# slimarm_apricot_dev.net
KiCad netlist of a schematic drawn in EasyEDA Pro
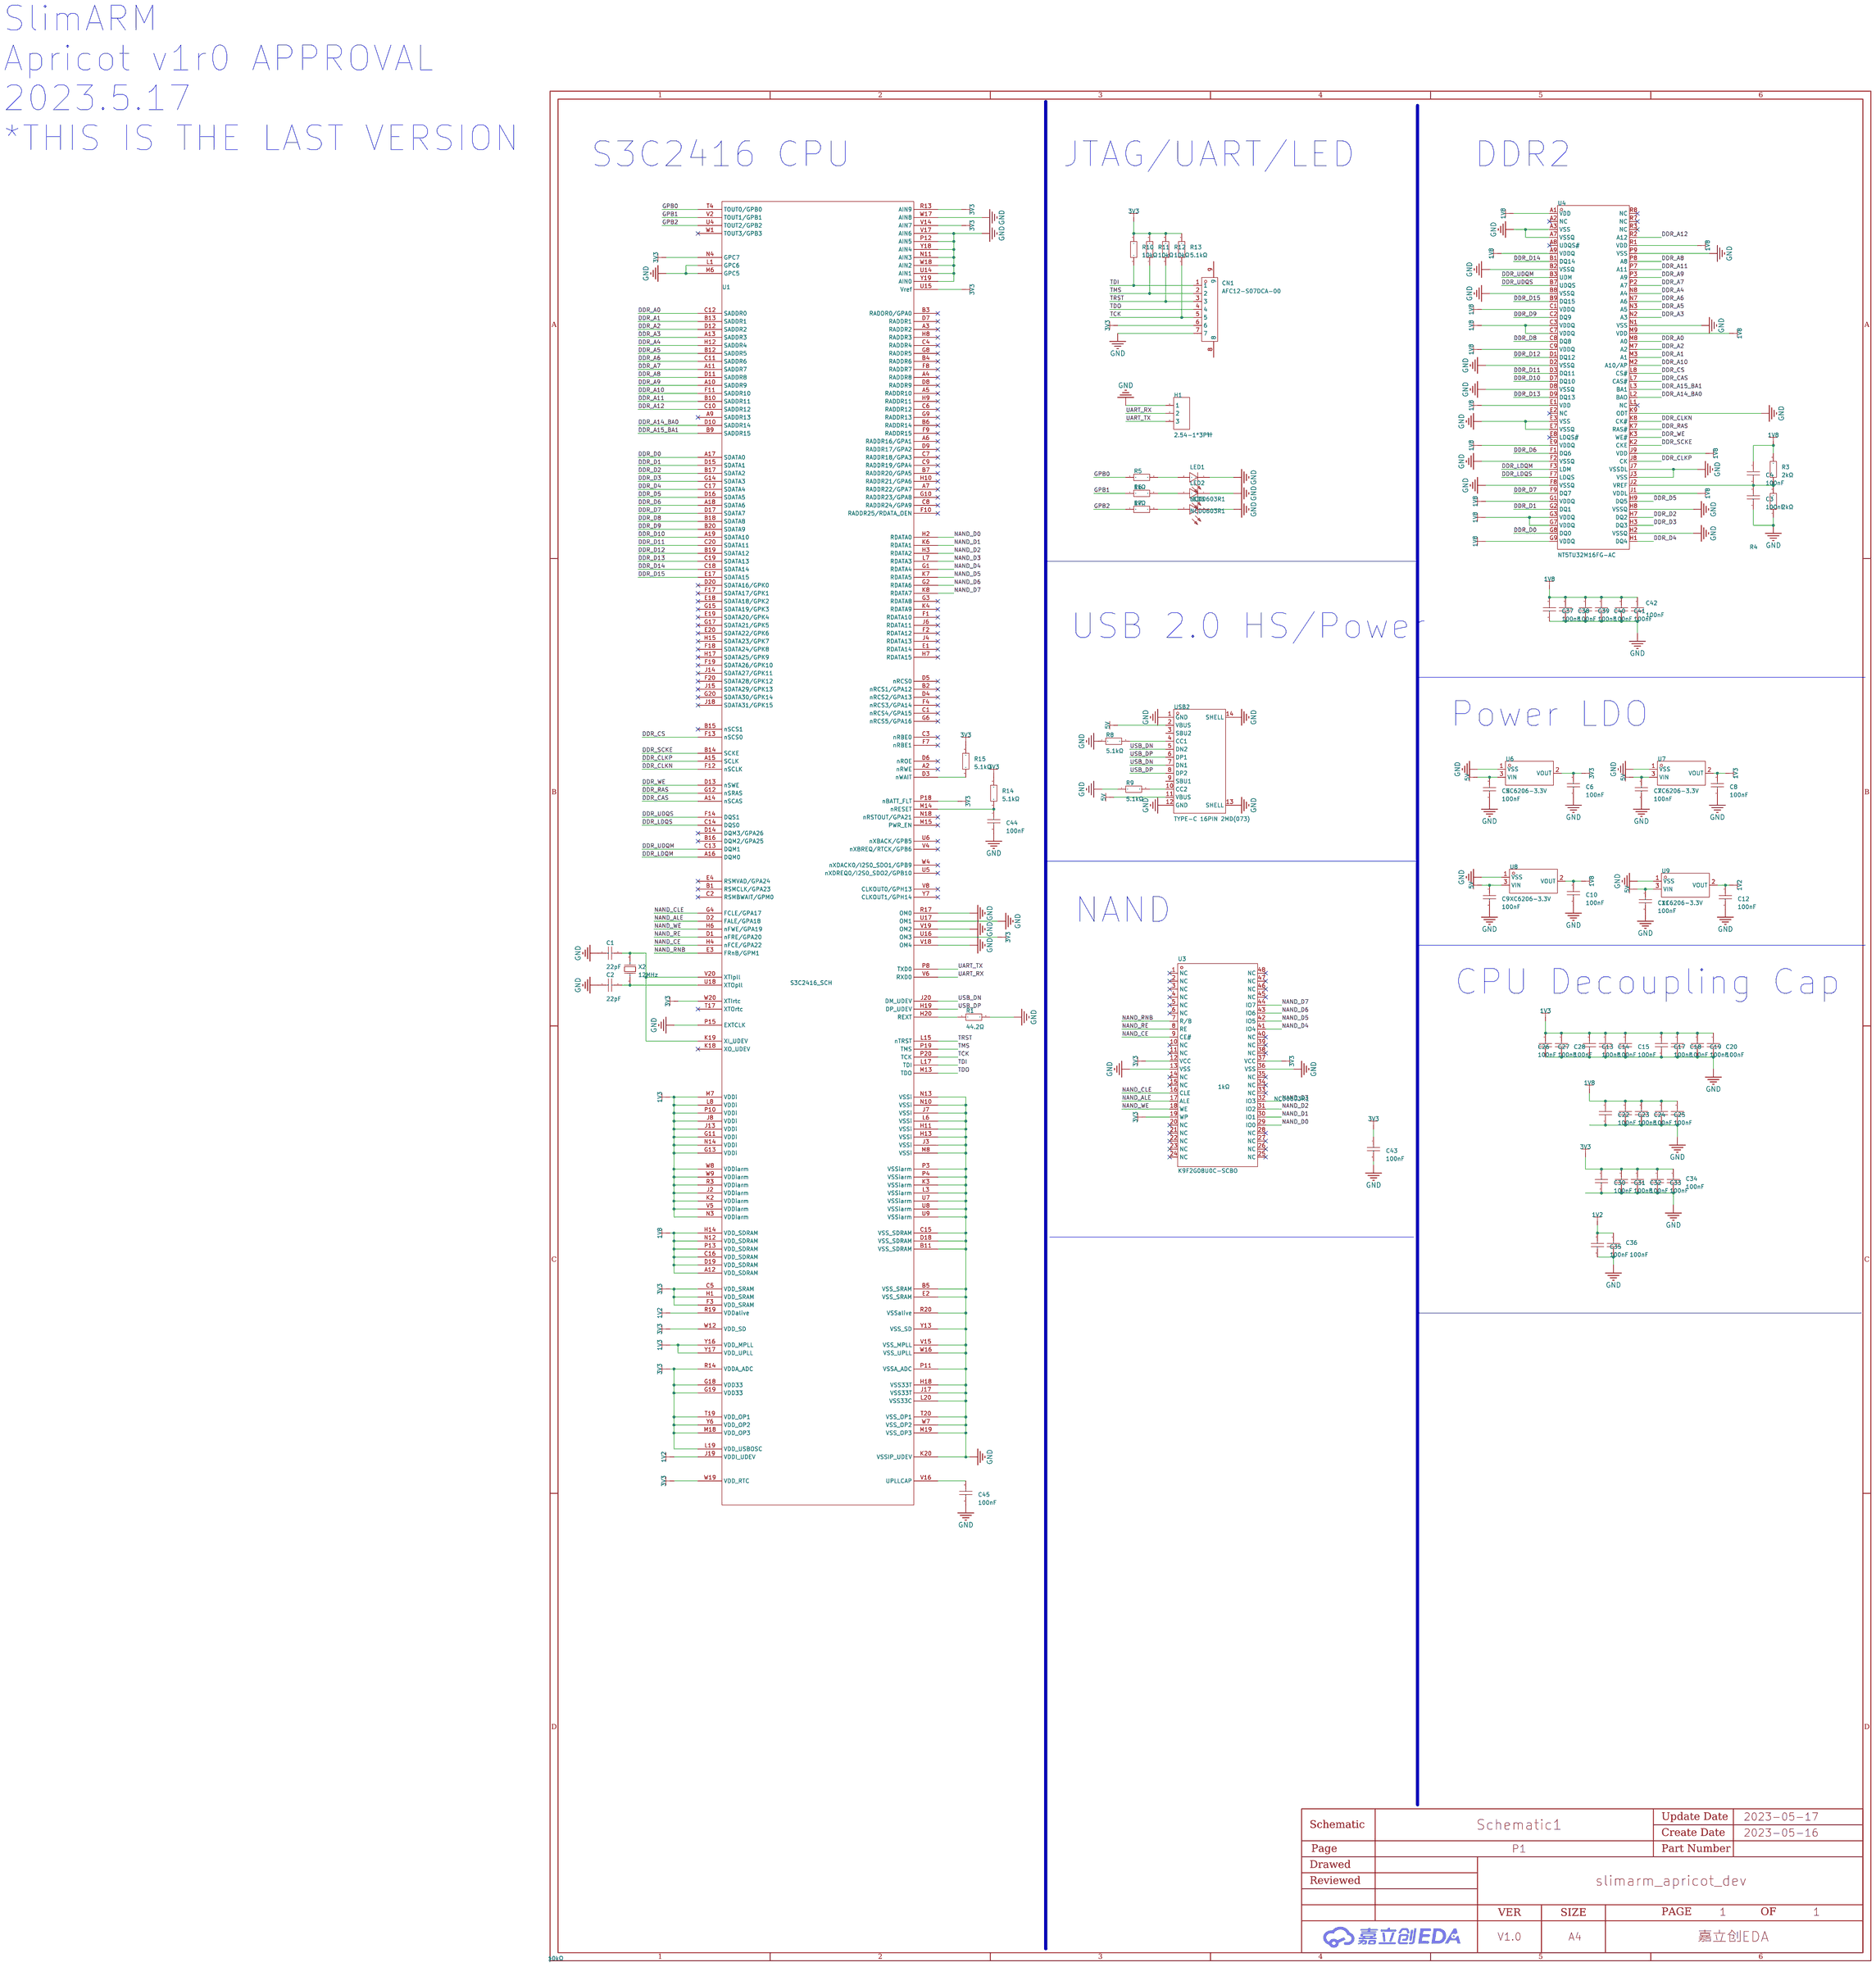
[diagram p0: schematic sheet]

(export (version "E")
  (design (tool "Eeschema 10.0.6"))
  (components
    (comp (ref "C1")
      (value "22pF")
      (footprint "easyedapro:C0402")
      (description "容值:22pF;精度:±5%;额定电压:50V;材质(温度系数):NP0;")
      (fields
        (field (name "Manufacturer Part") "CC0402JRNPO9BN220")
        (field (name "Manufacturer") "YAGEO(国巨)")
      )
      (libsource (lib "easyedapro") (part "CC0402JRNPO9BN220"))
    )
    (comp (ref "C2")
      (value "22pF")
      (footprint "easyedapro:C0402")
      (description "容值:22pF;精度:±5%;额定电压:50V;材质(温度系数):NP0;")
      (fields
        (field (name "Manufacturer Part") "CC0402JRNPO9BN220")
        (field (name "Manufacturer") "YAGEO(国巨)")
      )
      (libsource (lib "easyedapro") (part "CC0402JRNPO9BN220"))
    )
    (comp (ref "C3")
      (value "100nF")
      (footprint "easyedapro:C0402")
      (description "容值:22pF;精度:±5%;额定电压:50V;材质(温度系数):NP0;")
      (fields
        (field (name "Manufacturer Part") "CC0402JRNPO9BN220")
        (field (name "Manufacturer") "YAGEO(国巨)")
      )
      (libsource (lib "easyedapro") (part "CC0402JRNPO9BN220"))
    )
    (comp (ref "C4")
      (value "100nF")
      (footprint "easyedapro:C0402")
      (description "容值:22pF;精度:±5%;额定电压:50V;材质(温度系数):NP0;")
      (fields
        (field (name "Manufacturer Part") "CC0402JRNPO9BN220")
        (field (name "Manufacturer") "YAGEO(国巨)")
      )
      (libsource (lib "easyedapro") (part "CC0402JRNPO9BN220"))
    )
    (comp (ref "C5")
      (value "100nF")
      (footprint "easyedapro:C0402")
      (description "容值:22pF;精度:±5%;额定电压:50V;材质(温度系数):NP0;")
      (fields
        (field (name "Manufacturer Part") "CC0402JRNPO9BN220")
        (field (name "Manufacturer") "YAGEO(国巨)")
      )
      (libsource (lib "easyedapro") (part "CC0402JRNPO9BN220"))
    )
    (comp (ref "C6")
      (value "100nF")
      (footprint "easyedapro:C0402")
      (description "容值:22pF;精度:±5%;额定电压:50V;材质(温度系数):NP0;")
      (fields
        (field (name "Manufacturer Part") "CC0402JRNPO9BN220")
        (field (name "Manufacturer") "YAGEO(国巨)")
      )
      (libsource (lib "easyedapro") (part "CC0402JRNPO9BN220"))
    )
    (comp (ref "C7")
      (value "100nF")
      (footprint "easyedapro:C0402")
      (description "容值:22pF;精度:±5%;额定电压:50V;材质(温度系数):NP0;")
      (fields
        (field (name "Manufacturer Part") "CC0402JRNPO9BN220")
        (field (name "Manufacturer") "YAGEO(国巨)")
      )
      (libsource (lib "easyedapro") (part "CC0402JRNPO9BN220"))
    )
    (comp (ref "C8")
      (value "100nF")
      (footprint "easyedapro:C0402")
      (description "容值:22pF;精度:±5%;额定电压:50V;材质(温度系数):NP0;")
      (fields
        (field (name "Manufacturer Part") "CC0402JRNPO9BN220")
        (field (name "Manufacturer") "YAGEO(国巨)")
      )
      (libsource (lib "easyedapro") (part "CC0402JRNPO9BN220"))
    )
    (comp (ref "C9")
      (value "100nF")
      (footprint "easyedapro:C0402")
      (description "容值:22pF;精度:±5%;额定电压:50V;材质(温度系数):NP0;")
      (fields
        (field (name "Manufacturer Part") "CC0402JRNPO9BN220")
        (field (name "Manufacturer") "YAGEO(国巨)")
      )
      (libsource (lib "easyedapro") (part "CC0402JRNPO9BN220"))
    )
    (comp (ref "C10")
      (value "100nF")
      (footprint "easyedapro:C0402")
      (description "容值:22pF;精度:±5%;额定电压:50V;材质(温度系数):NP0;")
      (fields
        (field (name "Manufacturer Part") "CC0402JRNPO9BN220")
        (field (name "Manufacturer") "YAGEO(国巨)")
      )
      (libsource (lib "easyedapro") (part "CC0402JRNPO9BN220"))
    )
    (comp (ref "C11")
      (value "100nF")
      (footprint "easyedapro:C0402")
      (description "容值:22pF;精度:±5%;额定电压:50V;材质(温度系数):NP0;")
      (fields
        (field (name "Manufacturer Part") "CC0402JRNPO9BN220")
        (field (name "Manufacturer") "YAGEO(国巨)")
      )
      (libsource (lib "easyedapro") (part "CC0402JRNPO9BN220"))
    )
    (comp (ref "C12")
      (value "100nF")
      (footprint "easyedapro:C0402")
      (description "容值:22pF;精度:±5%;额定电压:50V;材质(温度系数):NP0;")
      (fields
        (field (name "Manufacturer Part") "CC0402JRNPO9BN220")
        (field (name "Manufacturer") "YAGEO(国巨)")
      )
      (libsource (lib "easyedapro") (part "CC0402JRNPO9BN220"))
    )
    (comp (ref "C13")
      (value "100nF")
      (footprint "easyedapro:C0402")
      (description "容值:22pF;精度:±5%;额定电压:50V;材质(温度系数):NP0;")
      (fields
        (field (name "Manufacturer Part") "CC0402JRNPO9BN220")
        (field (name "Manufacturer") "YAGEO(国巨)")
      )
      (libsource (lib "easyedapro") (part "CC0402JRNPO9BN220"))
    )
    (comp (ref "C14")
      (value "100nF")
      (footprint "easyedapro:C0402")
      (description "容值:22pF;精度:±5%;额定电压:50V;材质(温度系数):NP0;")
      (fields
        (field (name "Manufacturer Part") "CC0402JRNPO9BN220")
        (field (name "Manufacturer") "YAGEO(国巨)")
      )
      (libsource (lib "easyedapro") (part "CC0402JRNPO9BN220"))
    )
    (comp (ref "C15")
      (value "100nF")
      (footprint "easyedapro:C0402")
      (description "容值:22pF;精度:±5%;额定电压:50V;材质(温度系数):NP0;")
      (fields
        (field (name "Manufacturer Part") "CC0402JRNPO9BN220")
        (field (name "Manufacturer") "YAGEO(国巨)")
      )
      (libsource (lib "easyedapro") (part "CC0402JRNPO9BN220"))
    )
    (comp (ref "C17")
      (value "100nF")
      (footprint "easyedapro:C0402")
      (description "容值:22pF;精度:±5%;额定电压:50V;材质(温度系数):NP0;")
      (fields
        (field (name "Manufacturer Part") "CC0402JRNPO9BN220")
        (field (name "Manufacturer") "YAGEO(国巨)")
      )
      (libsource (lib "easyedapro") (part "CC0402JRNPO9BN220"))
    )
    (comp (ref "C18")
      (value "100nF")
      (footprint "easyedapro:C0402")
      (description "容值:22pF;精度:±5%;额定电压:50V;材质(温度系数):NP0;")
      (fields
        (field (name "Manufacturer Part") "CC0402JRNPO9BN220")
        (field (name "Manufacturer") "YAGEO(国巨)")
      )
      (libsource (lib "easyedapro") (part "CC0402JRNPO9BN220"))
    )
    (comp (ref "C19")
      (value "100nF")
      (footprint "easyedapro:C0402")
      (description "容值:22pF;精度:±5%;额定电压:50V;材质(温度系数):NP0;")
      (fields
        (field (name "Manufacturer Part") "CC0402JRNPO9BN220")
        (field (name "Manufacturer") "YAGEO(国巨)")
      )
      (libsource (lib "easyedapro") (part "CC0402JRNPO9BN220"))
    )
    (comp (ref "C20")
      (value "100nF")
      (footprint "easyedapro:C0402")
      (description "容值:22pF;精度:±5%;额定电压:50V;材质(温度系数):NP0;")
      (fields
        (field (name "Manufacturer Part") "CC0402JRNPO9BN220")
        (field (name "Manufacturer") "YAGEO(国巨)")
      )
      (libsource (lib "easyedapro") (part "CC0402JRNPO9BN220"))
    )
    (comp (ref "C22")
      (value "100nF")
      (footprint "easyedapro:C0402")
      (description "容值:22pF;精度:±5%;额定电压:50V;材质(温度系数):NP0;")
      (fields
        (field (name "Manufacturer Part") "CC0402JRNPO9BN220")
        (field (name "Manufacturer") "YAGEO(国巨)")
      )
      (libsource (lib "easyedapro") (part "CC0402JRNPO9BN220"))
    )
    (comp (ref "C23")
      (value "100nF")
      (footprint "easyedapro:C0402")
      (description "容值:22pF;精度:±5%;额定电压:50V;材质(温度系数):NP0;")
      (fields
        (field (name "Manufacturer Part") "CC0402JRNPO9BN220")
        (field (name "Manufacturer") "YAGEO(国巨)")
      )
      (libsource (lib "easyedapro") (part "CC0402JRNPO9BN220"))
    )
    (comp (ref "C24")
      (value "100nF")
      (footprint "easyedapro:C0402")
      (description "容值:22pF;精度:±5%;额定电压:50V;材质(温度系数):NP0;")
      (fields
        (field (name "Manufacturer Part") "CC0402JRNPO9BN220")
        (field (name "Manufacturer") "YAGEO(国巨)")
      )
      (libsource (lib "easyedapro") (part "CC0402JRNPO9BN220"))
    )
    (comp (ref "C25")
      (value "100nF")
      (footprint "easyedapro:C0402")
      (description "容值:22pF;精度:±5%;额定电压:50V;材质(温度系数):NP0;")
      (fields
        (field (name "Manufacturer Part") "CC0402JRNPO9BN220")
        (field (name "Manufacturer") "YAGEO(国巨)")
      )
      (libsource (lib "easyedapro") (part "CC0402JRNPO9BN220"))
    )
    (comp (ref "C26")
      (value "100nF")
      (footprint "easyedapro:C0402")
      (description "容值:22pF;精度:±5%;额定电压:50V;材质(温度系数):NP0;")
      (fields
        (field (name "Manufacturer Part") "CC0402JRNPO9BN220")
        (field (name "Manufacturer") "YAGEO(国巨)")
      )
      (libsource (lib "easyedapro") (part "CC0402JRNPO9BN220"))
    )
    (comp (ref "C27")
      (value "100nF")
      (footprint "easyedapro:C0402")
      (description "容值:22pF;精度:±5%;额定电压:50V;材质(温度系数):NP0;")
      (fields
        (field (name "Manufacturer Part") "CC0402JRNPO9BN220")
        (field (name "Manufacturer") "YAGEO(国巨)")
      )
      (libsource (lib "easyedapro") (part "CC0402JRNPO9BN220"))
    )
    (comp (ref "C28")
      (value "100nF")
      (footprint "easyedapro:C0402")
      (description "容值:22pF;精度:±5%;额定电压:50V;材质(温度系数):NP0;")
      (fields
        (field (name "Manufacturer Part") "CC0402JRNPO9BN220")
        (field (name "Manufacturer") "YAGEO(国巨)")
      )
      (libsource (lib "easyedapro") (part "CC0402JRNPO9BN220"))
    )
    (comp (ref "C30")
      (value "100nF")
      (footprint "easyedapro:C0402")
      (description "容值:22pF;精度:±5%;额定电压:50V;材质(温度系数):NP0;")
      (fields
        (field (name "Manufacturer Part") "CC0402JRNPO9BN220")
        (field (name "Manufacturer") "YAGEO(国巨)")
      )
      (libsource (lib "easyedapro") (part "CC0402JRNPO9BN220"))
    )
    (comp (ref "C31")
      (value "100nF")
      (footprint "easyedapro:C0402")
      (description "容值:22pF;精度:±5%;额定电压:50V;材质(温度系数):NP0;")
      (fields
        (field (name "Manufacturer Part") "CC0402JRNPO9BN220")
        (field (name "Manufacturer") "YAGEO(国巨)")
      )
      (libsource (lib "easyedapro") (part "CC0402JRNPO9BN220"))
    )
    (comp (ref "C32")
      (value "100nF")
      (footprint "easyedapro:C0402")
      (description "容值:22pF;精度:±5%;额定电压:50V;材质(温度系数):NP0;")
      (fields
        (field (name "Manufacturer Part") "CC0402JRNPO9BN220")
        (field (name "Manufacturer") "YAGEO(国巨)")
      )
      (libsource (lib "easyedapro") (part "CC0402JRNPO9BN220"))
    )
    (comp (ref "C33")
      (value "100nF")
      (footprint "easyedapro:C0402")
      (description "容值:22pF;精度:±5%;额定电压:50V;材质(温度系数):NP0;")
      (fields
        (field (name "Manufacturer Part") "CC0402JRNPO9BN220")
        (field (name "Manufacturer") "YAGEO(国巨)")
      )
      (libsource (lib "easyedapro") (part "CC0402JRNPO9BN220"))
    )
    (comp (ref "C34")
      (value "100nF")
      (footprint "easyedapro:C0402")
      (description "容值:22pF;精度:±5%;额定电压:50V;材质(温度系数):NP0;")
      (fields
        (field (name "Manufacturer Part") "CC0402JRNPO9BN220")
        (field (name "Manufacturer") "YAGEO(国巨)")
      )
      (libsource (lib "easyedapro") (part "CC0402JRNPO9BN220"))
    )
    (comp (ref "C35")
      (value "100nF")
      (footprint "easyedapro:C0402")
      (description "容值:22pF;精度:±5%;额定电压:50V;材质(温度系数):NP0;")
      (fields
        (field (name "Manufacturer Part") "CC0402JRNPO9BN220")
        (field (name "Manufacturer") "YAGEO(国巨)")
      )
      (libsource (lib "easyedapro") (part "CC0402JRNPO9BN220"))
    )
    (comp (ref "C36")
      (value "100nF")
      (footprint "easyedapro:C0402")
      (description "容值:22pF;精度:±5%;额定电压:50V;材质(温度系数):NP0;")
      (fields
        (field (name "Manufacturer Part") "CC0402JRNPO9BN220")
        (field (name "Manufacturer") "YAGEO(国巨)")
      )
      (libsource (lib "easyedapro") (part "CC0402JRNPO9BN220"))
    )
    (comp (ref "C37")
      (value "100nF")
      (footprint "easyedapro:C0402")
      (description "容值:22pF;精度:±5%;额定电压:50V;材质(温度系数):NP0;")
      (fields
        (field (name "Manufacturer Part") "CC0402JRNPO9BN220")
        (field (name "Manufacturer") "YAGEO(国巨)")
      )
      (libsource (lib "easyedapro") (part "CC0402JRNPO9BN220"))
    )
    (comp (ref "C38")
      (value "100nF")
      (footprint "easyedapro:C0402")
      (description "容值:22pF;精度:±5%;额定电压:50V;材质(温度系数):NP0;")
      (fields
        (field (name "Manufacturer Part") "CC0402JRNPO9BN220")
        (field (name "Manufacturer") "YAGEO(国巨)")
      )
      (libsource (lib "easyedapro") (part "CC0402JRNPO9BN220"))
    )
    (comp (ref "C39")
      (value "100nF")
      (footprint "easyedapro:C0402")
      (description "容值:22pF;精度:±5%;额定电压:50V;材质(温度系数):NP0;")
      (fields
        (field (name "Manufacturer Part") "CC0402JRNPO9BN220")
        (field (name "Manufacturer") "YAGEO(国巨)")
      )
      (libsource (lib "easyedapro") (part "CC0402JRNPO9BN220"))
    )
    (comp (ref "C40")
      (value "100nF")
      (footprint "easyedapro:C0402")
      (description "容值:22pF;精度:±5%;额定电压:50V;材质(温度系数):NP0;")
      (fields
        (field (name "Manufacturer Part") "CC0402JRNPO9BN220")
        (field (name "Manufacturer") "YAGEO(国巨)")
      )
      (libsource (lib "easyedapro") (part "CC0402JRNPO9BN220"))
    )
    (comp (ref "C41")
      (value "100nF")
      (footprint "easyedapro:C0402")
      (description "容值:22pF;精度:±5%;额定电压:50V;材质(温度系数):NP0;")
      (fields
        (field (name "Manufacturer Part") "CC0402JRNPO9BN220")
        (field (name "Manufacturer") "YAGEO(国巨)")
      )
      (libsource (lib "easyedapro") (part "CC0402JRNPO9BN220"))
    )
    (comp (ref "C42")
      (value "100nF")
      (footprint "easyedapro:C0402")
      (description "容值:22pF;精度:±5%;额定电压:50V;材质(温度系数):NP0;")
      (fields
        (field (name "Manufacturer Part") "CC0402JRNPO9BN220")
        (field (name "Manufacturer") "YAGEO(国巨)")
      )
      (libsource (lib "easyedapro") (part "CC0402JRNPO9BN220"))
    )
    (comp (ref "C43")
      (value "100nF")
      (footprint "easyedapro:C0402")
      (description "容值:22pF;精度:±5%;额定电压:50V;材质(温度系数):NP0;")
      (fields
        (field (name "Manufacturer Part") "CC0402JRNPO9BN220")
        (field (name "Manufacturer") "YAGEO(国巨)")
      )
      (libsource (lib "easyedapro") (part "CC0402JRNPO9BN220"))
    )
    (comp (ref "C44")
      (value "100nF")
      (footprint "easyedapro:C0402")
      (description "容值:22pF;精度:±5%;额定电压:50V;材质(温度系数):NP0;")
      (fields
        (field (name "Manufacturer Part") "CC0402JRNPO9BN220")
        (field (name "Manufacturer") "YAGEO(国巨)")
      )
      (libsource (lib "easyedapro") (part "CC0402JRNPO9BN220"))
    )
    (comp (ref "C45")
      (value "100nF")
      (footprint "easyedapro:C0402")
      (description "容值:22pF;精度:±5%;额定电压:50V;材质(温度系数):NP0;")
      (fields
        (field (name "Manufacturer Part") "CC0402JRNPO9BN220")
        (field (name "Manufacturer") "YAGEO(国巨)")
      )
      (libsource (lib "easyedapro") (part "CC0402JRNPO9BN220"))
    )
    (comp (ref "CN1")
      (value "AFC12-S07DCA-00")
      (footprint "easyedapro:CONN-SMD_AFC12-S07DCA-00")
      (description "参考系列:-;间距:1.25mm;插针结构:1x7P;排数:1;每排PIN数:7;行距:-;公母:公型插针;安装方式:卧贴;额定电流:1A;工作温度范围:-20°C~+85°C;")
      (fields (field (name "Manufacturer") "JS(钜硕电子)"))
      (libsource (lib "easyedapro") (part "AFC12-S07DCA-00"))
    )
    (comp (ref "H1")
      (value "2.54-1*3P针")
      (footprint "easyedapro:HDR-TH_3P-P2.54-V-M-1")
      (fields (field (name "Manufacturer") "BOOMELE(博穆精密)"))
      (libsource (lib "easyedapro") (part "Header-Male-2.54_1x3"))
    )
    (comp (ref "LED1")
      (value "NCD0603R1")
      (footprint "easyedapro:LED0603-RD_RED")
      (description "发光颜色:红灯;")
      (fields (field (name "Manufacturer") "国星光电"))
      (libsource (lib "easyedapro") (part "FC-DA1608HRK-620D"))
    )
    (comp (ref "LED2")
      (value "NCD0603R1")
      (footprint "easyedapro:LED0603-RD_RED")
      (description "发光颜色:红灯;")
      (fields (field (name "Manufacturer") "国星光电"))
      (libsource (lib "easyedapro") (part "FC-DA1608HRK-620D"))
    )
    (comp (ref "LED3")
      (value "NCD0603R1")
      (footprint "easyedapro:LED0603-RD_RED")
      (description "发光颜色:红灯;")
      (fields (field (name "Manufacturer") "国星光电"))
      (libsource (lib "easyedapro") (part "FC-DA1608HRK-620D"))
    )
    (comp (ref "R1")
      (value "44.2Ω")
      (footprint "easyedapro:R0402")
      (description "阻值:44.2Ω;精度:±1%;功率:62.5mW;")
      (fields (field (name "Manufacturer Part") "RCT0244R2FLF") (field (name "Manufacturer") "HKR"))
      (libsource (lib "easyedapro") (part "RCT0244R2FLF"))
    )
    (comp (ref "R3")
      (value "2kΩ")
      (footprint "easyedapro:R0402")
      (description "阻值:44.2Ω;精度:±1%;功率:62.5mW;")
      (fields (field (name "Manufacturer Part") "RCT0244R2FLF") (field (name "Manufacturer") "HKR"))
      (libsource (lib "easyedapro") (part "RCT0244R2FLF"))
    )
    (comp (ref "R4")
      (value "2kΩ")
      (footprint "easyedapro:R0402")
      (description "阻值:44.2Ω;精度:±1%;功率:62.5mW;")
      (fields (field (name "Manufacturer Part") "RCT0244R2FLF") (field (name "Manufacturer") "HKR"))
      (libsource (lib "easyedapro") (part "RCT0244R2FLF"))
    )
    (comp (ref "R5")
      (value "1kΩ")
      (footprint "easyedapro:R0603")
      (description "电阻类型:厚膜电阻;阻值:1kΩ;精度:±1%;功率:100mW;")
      (fields
        (field (name "Manufacturer Part") "0603WAF1001T5E")
        (field (name "Manufacturer") "UNI-ROYAL(厚声)")
      )
      (libsource (lib "easyedapro") (part "0603WAF1001T5E"))
    )
    (comp (ref "R6")
      (value "1kΩ")
      (footprint "easyedapro:R0603")
      (description "电阻类型:厚膜电阻;阻值:1kΩ;精度:±1%;功率:100mW;")
      (fields
        (field (name "Manufacturer Part") "0603WAF1001T5E")
        (field (name "Manufacturer") "UNI-ROYAL(厚声)")
      )
      (libsource (lib "easyedapro") (part "0603WAF1001T5E"))
    )
    (comp (ref "R7")
      (value "1kΩ")
      (footprint "easyedapro:R0603")
      (description "电阻类型:厚膜电阻;阻值:1kΩ;精度:±1%;功率:100mW;")
      (fields
        (field (name "Manufacturer Part") "0603WAF1001T5E")
        (field (name "Manufacturer") "UNI-ROYAL(厚声)")
      )
      (libsource (lib "easyedapro") (part "0603WAF1001T5E"))
    )
    (comp (ref "R8")
      (value "5.1kΩ")
      (footprint "easyedapro:R0402")
      (description "电阻类型:厚膜电阻;阻值:5.1kΩ;精度:±1%;功率:62.5mW;")
      (fields
        (field (name "Manufacturer Part") "0402WGF5101TCE")
        (field (name "Manufacturer") "UNI-ROYAL(厚声)")
      )
      (libsource (lib "easyedapro") (part "0402WGF5101TCE"))
    )
    (comp (ref "R9")
      (value "5.1kΩ")
      (footprint "easyedapro:R0402")
      (description "电阻类型:厚膜电阻;阻值:5.1kΩ;精度:±1%;功率:62.5mW;")
      (fields
        (field (name "Manufacturer Part") "0402WGF5101TCE")
        (field (name "Manufacturer") "UNI-ROYAL(厚声)")
      )
      (libsource (lib "easyedapro") (part "0402WGF5101TCE"))
    )
    (comp (ref "R10")
      (value "10kΩ")
      (footprint "easyedapro:R0402")
      (description "电阻类型:厚膜电阻;阻值:5.1kΩ;精度:±1%;功率:62.5mW;")
      (fields
        (field (name "Manufacturer Part") "0402WGF5101TCE")
        (field (name "Manufacturer") "UNI-ROYAL(厚声)")
      )
      (libsource (lib "easyedapro") (part "0402WGF5101TCE"))
    )
    (comp (ref "R11")
      (value "10kΩ")
      (footprint "easyedapro:R0402")
      (description "电阻类型:厚膜电阻;阻值:5.1kΩ;精度:±1%;功率:62.5mW;")
      (fields
        (field (name "Manufacturer Part") "0402WGF5101TCE")
        (field (name "Manufacturer") "UNI-ROYAL(厚声)")
      )
      (libsource (lib "easyedapro") (part "0402WGF5101TCE"))
    )
    (comp (ref "R12")
      (value "10kΩ")
      (footprint "easyedapro:R0402")
      (description "电阻类型:厚膜电阻;阻值:5.1kΩ;精度:±1%;功率:62.5mW;")
      (fields
        (field (name "Manufacturer Part") "0402WGF5101TCE")
        (field (name "Manufacturer") "UNI-ROYAL(厚声)")
      )
      (libsource (lib "easyedapro") (part "0402WGF5101TCE"))
    )
    (comp (ref "R13")
      (value "5.1kΩ")
      (footprint "easyedapro:R0402")
      (description "电阻类型:厚膜电阻;阻值:5.1kΩ;精度:±1%;功率:62.5mW;")
      (fields
        (field (name "Manufacturer Part") "0402WGF5101TCE")
        (field (name "Manufacturer") "UNI-ROYAL(厚声)")
      )
      (libsource (lib "easyedapro") (part "0402WGF5101TCE"))
    )
    (comp (ref "R14")
      (value "5.1kΩ")
      (footprint "easyedapro:R0402")
      (description "电阻类型:厚膜电阻;阻值:5.1kΩ;精度:±1%;功率:62.5mW;")
      (fields
        (field (name "Manufacturer Part") "0402WGF5101TCE")
        (field (name "Manufacturer") "UNI-ROYAL(厚声)")
      )
      (libsource (lib "easyedapro") (part "0402WGF5101TCE"))
    )
    (comp (ref "R15")
      (value "5.1kΩ")
      (footprint "easyedapro:R0402")
      (description "电阻类型:厚膜电阻;阻值:5.1kΩ;精度:±1%;功率:62.5mW;")
      (fields
        (field (name "Manufacturer Part") "0402WGF5101TCE")
        (field (name "Manufacturer") "UNI-ROYAL(厚声)")
      )
      (libsource (lib "easyedapro") (part "0402WGF5101TCE"))
    )
    (comp (ref "U1") (value "S3C2416_SCH") (libsource (lib "easyedapro") (part "S3C2416_SCH")))
    (comp (ref "U3")
      (value "K9F2G08U0C-SCBO")
      (footprint "easyedapro:TSOP-48_L12.0-W18.4-P0.50-LS20.0-BL")
      (description "存储器构架(格式):FLASH;存储器接口类型:Parallel;存储器容量:2Gb (256M x 8);存储器类型:Non-Volatile;")
      (libsource (lib "easyedapro") (part "K9F2G08UOC-SCBO"))
    )
    (comp (ref "U4")
      (value "NT5TU32M16FG-AC")
      (footprint "easyedapro:VFBGA-84_L7.5-W12.2-P0.80-TL_NANYA_NT5TU32M16FG")
      (fields (field (name "Manufacturer") "Nanya(南亚科技)"))
      (libsource (lib "easyedapro") (part "NT5TU32M16FG-AC"))
    )
    (comp (ref "U6")
      (value "XC6206-3.3V")
      (footprint "easyedapro:SSOT-3_L2.9-W1.6-P0.95-LS2.8-BR")
      (description "输出类型:固定;输出极性:正;最大输入电压:6V;输出电压:3.3V;输出电流:250mA;")
      (fields (field (name "Manufacturer") "YONGYUTAI(永裕泰)"))
      (libsource (lib "easyedapro") (part "XC6206-3.3V"))
    )
    (comp (ref "U7")
      (value "XC6206-3.3V")
      (footprint "easyedapro:SSOT-3_L2.9-W1.6-P0.95-LS2.8-BR")
      (description "输出类型:固定;输出极性:正;最大输入电压:6V;输出电压:3.3V;输出电流:250mA;")
      (fields (field (name "Manufacturer") "YONGYUTAI(永裕泰)"))
      (libsource (lib "easyedapro") (part "XC6206-3.3V"))
    )
    (comp (ref "U8")
      (value "XC6206-3.3V")
      (footprint "easyedapro:SSOT-3_L2.9-W1.6-P0.95-LS2.8-BR")
      (description "输出类型:固定;输出极性:正;最大输入电压:6V;输出电压:3.3V;输出电流:250mA;")
      (fields (field (name "Manufacturer") "YONGYUTAI(永裕泰)"))
      (libsource (lib "easyedapro") (part "XC6206-3.3V"))
    )
    (comp (ref "U9")
      (value "XC6206-3.3V")
      (footprint "easyedapro:SSOT-3_L2.9-W1.6-P0.95-LS2.8-BR")
      (description "输出类型:固定;输出极性:正;最大输入电压:6V;输出电压:3.3V;输出电流:250mA;")
      (fields (field (name "Manufacturer") "YONGYUTAI(永裕泰)"))
      (libsource (lib "easyedapro") (part "XC6206-3.3V"))
    )
    (comp (ref "USB2")
      (value "TYPE-C 16PIN 2MD(073)")
      (footprint "easyedapro:USB-C-SMD_TYPE-C-6PIN-2MD-073")
      (description "连接器类型:Type-C;标准:-;公母:母座;触点数量:16;端口数量:1;安装方式:卧贴;额定电流 - 电源:5A;工作温度范围:-25°C~+85°C;")
      (fields (field (name "Manufacturer") "SHOU HAN(首韩)"))
      (libsource (lib "easyedapro") (part "TYPE-C 16PIN 2MD(073)"))
    )
    (comp (ref "X2")
      (value "12MHz")
      (footprint "easyedapro:CRYSTAL-SMD_L5.0-W3.2")
      (description "频率:8MHz;频率公差:±10ppm;负载电容:20pF;")
      (fields (field (name "Manufacturer Part") "X50328MSB2GI") (field (name "Manufacturer") "YXC(扬兴晶振)"))
      (libsource (lib "easyedapro") (part "X50328MSB2GI"))
    )
  )
  (nets
    (net (code "1") (name "/DDR_A0") (class "Default")
      (node (ref "U1") (pin "C12") (pinfunction "SADDR0_C12") (pintype "input"))
      (node (ref "U4") (pin "M8") (pinfunction "A0_M8") (pintype "input"))
    )
    (net (code "2") (name "/DDR_A1") (class "Default")
      (node (ref "U1") (pin "B13") (pinfunction "SADDR1_B13") (pintype "input"))
      (node (ref "U4") (pin "M3") (pinfunction "A1_M3") (pintype "input"))
    )
    (net (code "3") (name "/DDR_A2") (class "Default")
      (node (ref "U1") (pin "D12") (pinfunction "SADDR2_D12") (pintype "input"))
      (node (ref "U4") (pin "M7") (pinfunction "A2_M7") (pintype "input"))
    )
    (net (code "4") (name "/DDR_A3") (class "Default")
      (node (ref "U1") (pin "A13") (pinfunction "SADDR3_A13") (pintype "input"))
      (node (ref "U4") (pin "N2") (pinfunction "A3_N2") (pintype "input"))
    )
    (net (code "5") (name "/DDR_A4") (class "Default")
      (node (ref "U1") (pin "H12") (pinfunction "SADDR4_H12") (pintype "input"))
      (node (ref "U4") (pin "N8") (pinfunction "A4_N8") (pintype "input"))
    )
    (net (code "6") (name "/DDR_A5") (class "Default")
      (node (ref "U1") (pin "B12") (pinfunction "SADDR5_B12") (pintype "input"))
      (node (ref "U4") (pin "N3") (pinfunction "A5_N3") (pintype "input"))
    )
    (net (code "7") (name "/DDR_A6") (class "Default")
      (node (ref "U1") (pin "C11") (pinfunction "SADDR6_C11") (pintype "input"))
      (node (ref "U4") (pin "N7") (pinfunction "A6_N7") (pintype "input"))
    )
    (net (code "8") (name "/DDR_A7") (class "Default")
      (node (ref "U1") (pin "A11") (pinfunction "SADDR7_A11") (pintype "input"))
      (node (ref "U4") (pin "P2") (pinfunction "A7_P2") (pintype "input"))
    )
    (net (code "9") (name "/DDR_A8") (class "Default")
      (node (ref "U1") (pin "D11") (pinfunction "SADDR8_D11") (pintype "input"))
      (node (ref "U4") (pin "P8") (pinfunction "A8_P8") (pintype "input"))
    )
    (net (code "10") (name "/DDR_A9") (class "Default")
      (node (ref "U1") (pin "A10") (pinfunction "SADDR9_A10") (pintype "input"))
      (node (ref "U4") (pin "P3") (pinfunction "A9_P3") (pintype "input"))
    )
    (net (code "11") (name "/DDR_A10") (class "Default")
      (node (ref "U1") (pin "F11") (pinfunction "SADDR10_F11") (pintype "input"))
      (node (ref "U4") (pin "M2") (pinfunction "A10/AP_M2") (pintype "input"))
    )
    (net (code "12") (name "/DDR_A11") (class "Default")
      (node (ref "U1") (pin "B10") (pinfunction "SADDR11_B10") (pintype "input"))
      (node (ref "U4") (pin "P7") (pinfunction "A11_P7") (pintype "input"))
    )
    (net (code "13") (name "/DDR_A12") (class "Default")
      (node (ref "U1") (pin "C10") (pinfunction "SADDR12_C10") (pintype "input"))
      (node (ref "U4") (pin "R2") (pinfunction "A12_R2") (pintype "input"))
    )
    (net (code "14") (name "/DDR_A14_BA0") (class "Default")
      (node (ref "U1") (pin "D10") (pinfunction "SADDR14_D10") (pintype "input"))
      (node (ref "U4") (pin "L2") (pinfunction "BAO_L2") (pintype "input"))
    )
    (net (code "15") (name "/DDR_A15_BA1") (class "Default")
      (node (ref "U1") (pin "B9") (pinfunction "SADDR15_B9") (pintype "input"))
      (node (ref "U4") (pin "L3") (pinfunction "BA1_L3") (pintype "input"))
    )
    (net (code "16") (name "/DDR_CAS") (class "Default")
      (node (ref "U1") (pin "A14") (pinfunction "nSCAS_A14") (pintype "input"))
      (node (ref "U4") (pin "L7") (pinfunction "CAS#_L7") (pintype "input"))
    )
    (net (code "17") (name "/DDR_CLKN") (class "Default")
      (node (ref "U1") (pin "F12") (pinfunction "nSCLK_F12") (pintype "input"))
      (node (ref "U4") (pin "K8") (pinfunction "CK#_K8") (pintype "input"))
    )
    (net (code "18") (name "/DDR_CLKP") (class "Default")
      (node (ref "U1") (pin "A15") (pinfunction "SCLK_A15") (pintype "input"))
      (node (ref "U4") (pin "J8") (pinfunction "CK_J8") (pintype "input"))
    )
    (net (code "19") (name "/DDR_CS") (class "Default")
      (node (ref "U1") (pin "F13") (pinfunction "nSCS0_F13") (pintype "input"))
      (node (ref "U4") (pin "L8") (pinfunction "CS#_L8") (pintype "input"))
    )
    (net (code "20") (name "/DDR_D0") (class "Default")
      (node (ref "U1") (pin "A17") (pinfunction "SDATA0_A17") (pintype "input"))
      (node (ref "U4") (pin "G8") (pinfunction "DQ0_G8") (pintype "input"))
    )
    (net (code "21") (name "/DDR_D1") (class "Default")
      (node (ref "U1") (pin "D15") (pinfunction "SDATA1_D15") (pintype "input"))
      (node (ref "U4") (pin "G2") (pinfunction "DQ1_G2") (pintype "input"))
    )
    (net (code "22") (name "/DDR_D2") (class "Default")
      (node (ref "U1") (pin "B17") (pinfunction "SDATA2_B17") (pintype "input"))
      (node (ref "U4") (pin "H7") (pinfunction "DQ2_H7") (pintype "input"))
    )
    (net (code "23") (name "/DDR_D3") (class "Default")
      (node (ref "U1") (pin "G14") (pinfunction "SDATA3_G14") (pintype "input"))
      (node (ref "U4") (pin "H3") (pinfunction "DQ3_H3") (pintype "input"))
    )
    (net (code "24") (name "/DDR_D4") (class "Default")
      (node (ref "U1") (pin "C17") (pinfunction "SDATA4_C17") (pintype "input"))
      (node (ref "U4") (pin "H1") (pinfunction "DQ4_H1") (pintype "input"))
    )
    (net (code "25") (name "/DDR_D5") (class "Default")
      (node (ref "U1") (pin "D16") (pinfunction "SDATA5_D16") (pintype "input"))
      (node (ref "U4") (pin "H9") (pinfunction "DQ5_H9") (pintype "input"))
    )
    (net (code "26") (name "/DDR_D6") (class "Default")
      (node (ref "U1") (pin "A18") (pinfunction "SDATA6_A18") (pintype "input"))
      (node (ref "U4") (pin "F1") (pinfunction "DQ6_F1") (pintype "input"))
    )
    (net (code "27") (name "/DDR_D7") (class "Default")
      (node (ref "U1") (pin "D17") (pinfunction "SDATA7_D17") (pintype "input"))
      (node (ref "U4") (pin "F9") (pinfunction "DQ7_F9") (pintype "input"))
    )
    (net (code "28") (name "/DDR_D8") (class "Default")
      (node (ref "U1") (pin "B18") (pinfunction "SDATA8_B18") (pintype "input"))
      (node (ref "U4") (pin "C8") (pinfunction "DQ8_C8") (pintype "input"))
    )
    (net (code "29") (name "/DDR_D9") (class "Default")
      (node (ref "U1") (pin "B20") (pinfunction "SDATA9_B20") (pintype "input"))
      (node (ref "U4") (pin "C2") (pinfunction "DQ9_C2") (pintype "input"))
    )
    (net (code "30") (name "/DDR_D10") (class "Default")
      (node (ref "U1") (pin "A19") (pinfunction "SDATA10_A19") (pintype "input"))
      (node (ref "U4") (pin "D7") (pinfunction "DQ10_D7") (pintype "input"))
    )
    (net (code "31") (name "/DDR_D11") (class "Default")
      (node (ref "U1") (pin "C20") (pinfunction "SDATA11_C20") (pintype "input"))
      (node (ref "U4") (pin "D3") (pinfunction "DQ11_D3") (pintype "input"))
    )
    (net (code "32") (name "/DDR_D12") (class "Default")
      (node (ref "U1") (pin "B19") (pinfunction "SDATA12_B19") (pintype "input"))
      (node (ref "U4") (pin "D1") (pinfunction "DQ12_D1") (pintype "input"))
    )
    (net (code "33") (name "/DDR_D13") (class "Default")
      (node (ref "U1") (pin "C19") (pinfunction "SDATA13_C19") (pintype "input"))
      (node (ref "U4") (pin "D9") (pinfunction "DQ13_D9") (pintype "input"))
    )
    (net (code "34") (name "/DDR_D14") (class "Default")
      (node (ref "U1") (pin "C18") (pinfunction "SDATA14_C18") (pintype "input"))
      (node (ref "U4") (pin "B1") (pinfunction "DQ14_B1") (pintype "input"))
    )
    (net (code "35") (name "/DDR_D15") (class "Default")
      (node (ref "U1") (pin "E17") (pinfunction "SDATA15_E17") (pintype "input"))
      (node (ref "U4") (pin "B9") (pinfunction "DQ15_B9") (pintype "input"))
    )
    (net (code "36") (name "/DDR_LDQM") (class "Default")
      (node (ref "U1") (pin "A16") (pinfunction "DQM0_A16") (pintype "input"))
      (node (ref "U4") (pin "F3") (pinfunction "LDM_F3") (pintype "input"))
    )
    (net (code "37") (name "/DDR_LDQS") (class "Default")
      (node (ref "U1") (pin "C14") (pinfunction "DQS0_C14") (pintype "input"))
      (node (ref "U4") (pin "F7") (pinfunction "LDQS_F7") (pintype "input"))
    )
    (net (code "38") (name "/DDR_RAS") (class "Default")
      (node (ref "U1") (pin "G12") (pinfunction "nSRAS_G12") (pintype "input"))
      (node (ref "U4") (pin "K7") (pinfunction "RAS#_K7") (pintype "input"))
    )
    (net (code "39") (name "/DDR_SCKE") (class "Default")
      (node (ref "U1") (pin "B14") (pinfunction "SCKE_B14") (pintype "input"))
      (node (ref "U4") (pin "K2") (pinfunction "CKE_K2") (pintype "input"))
    )
    (net (code "40") (name "/DDR_UDQM") (class "Default")
      (node (ref "U1") (pin "C13") (pinfunction "DQM1_C13") (pintype "input"))
      (node (ref "U4") (pin "B3") (pinfunction "UDM_B3") (pintype "input"))
    )
    (net (code "41") (name "/DDR_UDQS") (class "Default")
      (node (ref "U1") (pin "F14") (pinfunction "DQS1_F14") (pintype "input"))
      (node (ref "U4") (pin "B7") (pinfunction "UDQS_B7") (pintype "input"))
    )
    (net (code "42") (name "/DDR_WE") (class "Default")
      (node (ref "U1") (pin "D13") (pinfunction "nSWE_D13") (pintype "input"))
      (node (ref "U4") (pin "K3") (pinfunction "WE#_K3") (pintype "input"))
    )
    (net (code "43") (name "/GPB0") (class "Default")
      (node (ref "R5") (pin "1") (pinfunction "1_1") (pintype "input"))
      (node (ref "U1") (pin "T4") (pinfunction "TOUT0/GPB0_T4") (pintype "input"))
    )
    (net (code "44") (name "/GPB1") (class "Default")
      (node (ref "R6") (pin "1") (pinfunction "1_1") (pintype "input"))
      (node (ref "U1") (pin "V2") (pinfunction "TOUT1/GPB1_V2") (pintype "input"))
    )
    (net (code "45") (name "/GPB2") (class "Default")
      (node (ref "R7") (pin "1") (pinfunction "1_1") (pintype "input"))
      (node (ref "U1") (pin "U4") (pinfunction "TOUT2/GPB2_U4") (pintype "input"))
    )
    (net (code "46") (name "/NAND_ALE") (class "Default")
      (node (ref "U1") (pin "D2") (pinfunction "FALE/GPA18_D2") (pintype "input"))
      (node (ref "U3") (pin "17") (pinfunction "ALE_17") (pintype "input"))
    )
    (net (code "47") (name "/NAND_CE") (class "Default")
      (node (ref "U1") (pin "H4") (pinfunction "nFCE/GPA22_H4") (pintype "input"))
      (node (ref "U3") (pin "9") (pinfunction "CE#_9") (pintype "input"))
    )
    (net (code "48") (name "/NAND_CLE") (class "Default")
      (node (ref "U1") (pin "G4") (pinfunction "FCLE/GPA17_G4") (pintype "input"))
      (node (ref "U3") (pin "16") (pinfunction "CLE_16") (pintype "input"))
    )
    (net (code "49") (name "/NAND_D0") (class "Default")
      (node (ref "U1") (pin "H2") (pinfunction "RDATA0_H2") (pintype "input"))
      (node (ref "U3") (pin "29") (pinfunction "IO0_29") (pintype "input"))
    )
    (net (code "50") (name "/NAND_D1") (class "Default")
      (node (ref "U1") (pin "K6") (pinfunction "RDATA1_K6") (pintype "input"))
      (node (ref "U3") (pin "30") (pinfunction "IO1_30") (pintype "input"))
    )
    (net (code "51") (name "/NAND_D2") (class "Default")
      (node (ref "U1") (pin "H3") (pinfunction "RDATA2_H3") (pintype "input"))
      (node (ref "U3") (pin "31") (pinfunction "IO2_31") (pintype "input"))
    )
    (net (code "52") (name "/NAND_D3") (class "Default")
      (node (ref "U1") (pin "L7") (pinfunction "RDATA3_L7") (pintype "input"))
      (node (ref "U3") (pin "32") (pinfunction "IO3_32") (pintype "input"))
    )
    (net (code "53") (name "/NAND_D4") (class "Default")
      (node (ref "U1") (pin "G1") (pinfunction "RDATA4_G1") (pintype "input"))
      (node (ref "U3") (pin "41") (pinfunction "IO4_41") (pintype "input"))
    )
    (net (code "54") (name "/NAND_D5") (class "Default")
      (node (ref "U1") (pin "K7") (pinfunction "RDATA5_K7") (pintype "input"))
      (node (ref "U3") (pin "42") (pinfunction "IO5_42") (pintype "input"))
    )
    (net (code "55") (name "/NAND_D6") (class "Default")
      (node (ref "U1") (pin "G2") (pinfunction "RDATA6_G2") (pintype "input"))
      (node (ref "U3") (pin "43") (pinfunction "IO6_43") (pintype "input"))
    )
    (net (code "56") (name "/NAND_D7") (class "Default")
      (node (ref "U1") (pin "K8") (pinfunction "RDATA7_K8") (pintype "input"))
      (node (ref "U3") (pin "44") (pinfunction "IO7_44") (pintype "input"))
    )
    (net (code "57") (name "/NAND_RE") (class "Default")
      (node (ref "U1") (pin "D1") (pinfunction "nFRE/GPA20_D1") (pintype "input"))
      (node (ref "U3") (pin "8") (pinfunction "RE_8") (pintype "input"))
    )
    (net (code "58") (name "/NAND_RNB") (class "Default")
      (node (ref "U1") (pin "E3") (pinfunction "FRnB/GPM1_E3") (pintype "input"))
      (node (ref "U3") (pin "7") (pinfunction "R/B_7") (pintype "input"))
    )
    (net (code "59") (name "/NAND_WE") (class "Default")
      (node (ref "U1") (pin "H6") (pinfunction "nFWE/GPA19_H6") (pintype "input"))
      (node (ref "U3") (pin "18") (pinfunction "WE_18") (pintype "input"))
    )
    (net (code "60") (name "/TCK") (class "Default")
      (node (ref "CN1") (pin "5") (pinfunction "5_5") (pintype "input"))
      (node (ref "R13") (pin "1") (pinfunction "1_1") (pintype "input"))
      (node (ref "U1") (pin "P20") (pinfunction "TCK_P20") (pintype "input"))
    )
    (net (code "61") (name "/TDI") (class "Default")
      (node (ref "CN1") (pin "1") (pinfunction "1_1") (pintype "input"))
      (node (ref "R10") (pin "1") (pinfunction "1_1") (pintype "input"))
      (node (ref "U1") (pin "L17") (pinfunction "TDI_L17") (pintype "input"))
    )
    (net (code "62") (name "/TDO") (class "Default")
      (node (ref "CN1") (pin "4") (pinfunction "4_4") (pintype "input"))
      (node (ref "U1") (pin "M13") (pinfunction "TDO_M13") (pintype "output"))
    )
    (net (code "63") (name "/TMS") (class "Default")
      (node (ref "CN1") (pin "2") (pinfunction "2_2") (pintype "input"))
      (node (ref "R11") (pin "1") (pinfunction "1_1") (pintype "input"))
      (node (ref "U1") (pin "P19") (pinfunction "TMS_P19") (pintype "input"))
    )
    (net (code "64") (name "/TRST") (class "Default")
      (node (ref "CN1") (pin "3") (pinfunction "3_3") (pintype "input"))
      (node (ref "R12") (pin "1") (pinfunction "1_1") (pintype "input"))
      (node (ref "U1") (pin "L15") (pinfunction "nTRST_L15") (pintype "input"))
    )
    (net (code "65") (name "/UART_RX") (class "Default")
      (node (ref "H1") (pin "2") (pinfunction "2_2") (pintype "input"))
      (node (ref "U1") (pin "V6") (pinfunction "RXD0_V6") (pintype "input"))
    )
    (net (code "66") (name "/UART_TX") (class "Default")
      (node (ref "H1") (pin "3") (pinfunction "3_3") (pintype "input"))
      (node (ref "U1") (pin "P8") (pinfunction "TXD0_P8") (pintype "output"))
    )
    (net (code "67") (name "/USB_DN") (class "Default")
      (node (ref "U1") (pin "J20") (pinfunction "DM_UDEV_J20") (pintype "bidirectional"))
      (node (ref "USB2") (pin "5") (pinfunction "DN2_5") (pintype "input"))
      (node (ref "USB2") (pin "7") (pinfunction "DN1_7") (pintype "input"))
    )
    (net (code "68") (name "/USB_DP") (class "Default")
      (node (ref "U1") (pin "H19") (pinfunction "DP_UDEV_H19") (pintype "bidirectional"))
      (node (ref "USB2") (pin "6") (pinfunction "DP1_6") (pintype "input"))
      (node (ref "USB2") (pin "8") (pinfunction "DP2_8") (pintype "input"))
    )
    (net (code "69") (name "1V2") (class "Default")
      (node (ref "C12") (pin "1") (pinfunction "1_1") (pintype "input"))
      (node (ref "C35") (pin "1") (pinfunction "1_1") (pintype "input"))
      (node (ref "C36") (pin "1") (pinfunction "1_1") (pintype "input"))
      (node (ref "U1") (pin "J19") (pinfunction "VDDI_UDEV_J19") (pintype "input"))
      (node (ref "U1") (pin "R19") (pinfunction "VDDalive_R19") (pintype "input"))
      (node (ref "U9") (pin "2") (pinfunction "VOUT_2") (pintype "input"))
    )
    (net (code "70") (name "1V3") (class "Default")
      (node (ref "C13") (pin "1") (pinfunction "1_1") (pintype "input"))
      (node (ref "C14") (pin "1") (pinfunction "1_1") (pintype "input"))
      (node (ref "C15") (pin "1") (pinfunction "1_1") (pintype "input"))
      (node (ref "C17") (pin "1") (pinfunction "1_1") (pintype "input"))
      (node (ref "C18") (pin "1") (pinfunction "1_1") (pintype "input"))
      (node (ref "C19") (pin "1") (pinfunction "1_1") (pintype "input"))
      (node (ref "C20") (pin "1") (pinfunction "1_1") (pintype "input"))
      (node (ref "C27") (pin "1") (pinfunction "1_1") (pintype "input"))
      (node (ref "C28") (pin "1") (pinfunction "1_1") (pintype "input"))
      (node (ref "C8") (pin "1") (pinfunction "1_1") (pintype "input"))
      (node (ref "U1") (pin "G11") (pinfunction "VDDi_G11") (pintype "input"))
      (node (ref "U1") (pin "G13") (pinfunction "VDDi_G13") (pintype "input"))
      (node (ref "U1") (pin "J13") (pinfunction "VDDi_J13") (pintype "input"))
      (node (ref "U1") (pin "J2") (pinfunction "VDDiarm_J2") (pintype "input"))
      (node (ref "U1") (pin "J8") (pinfunction "VDDi_J8") (pintype "input"))
      (node (ref "U1") (pin "K2") (pinfunction "VDDiarm_K2") (pintype "input"))
      (node (ref "U1") (pin "L8") (pinfunction "VDDi_L8") (pintype "input"))
      (node (ref "U1") (pin "M7") (pinfunction "VDDi_M7") (pintype "input"))
      (node (ref "U1") (pin "N14") (pinfunction "VDDi_N14") (pintype "input"))
      (node (ref "U1") (pin "N3") (pinfunction "VDDiarm_N3") (pintype "input"))
      (node (ref "U1") (pin "P10") (pinfunction "VDDi_P10") (pintype "input"))
      (node (ref "U1") (pin "R3") (pinfunction "VDDiarm_R3") (pintype "input"))
      (node (ref "U1") (pin "V5") (pinfunction "VDDiarm_V5") (pintype "input"))
      (node (ref "U1") (pin "W8") (pinfunction "VDDiarm_W8") (pintype "input"))
      (node (ref "U1") (pin "W9") (pinfunction "VDDiarm_W9") (pintype "input"))
      (node (ref "U1") (pin "Y16") (pinfunction "VDD_MPLL_Y16") (pintype "input"))
      (node (ref "U1") (pin "Y17") (pinfunction "VDD_UPLL_Y17") (pintype "input"))
      (node (ref "U7") (pin "2") (pinfunction "VOUT_2") (pintype "input"))
    )
    (net (code "71") (name "1V8") (class "Default")
      (node (ref "C10") (pin "1") (pinfunction "1_1") (pintype "input"))
      (node (ref "C22") (pin "1") (pinfunction "1_1") (pintype "input"))
      (node (ref "C23") (pin "1") (pinfunction "1_1") (pintype "input"))
      (node (ref "C24") (pin "1") (pinfunction "1_1") (pintype "input"))
      (node (ref "C25") (pin "1") (pinfunction "1_1") (pintype "input"))
      (node (ref "C26") (pin "1") (pinfunction "1_1") (pintype "input"))
      (node (ref "C37") (pin "1") (pinfunction "1_1") (pintype "input"))
      (node (ref "C38") (pin "1") (pinfunction "1_1") (pintype "input"))
      (node (ref "C39") (pin "1") (pinfunction "1_1") (pintype "input"))
      (node (ref "C4") (pin "1") (pinfunction "1_1") (pintype "input"))
      (node (ref "C40") (pin "1") (pinfunction "1_1") (pintype "input"))
      (node (ref "C41") (pin "1") (pinfunction "1_1") (pintype "input"))
      (node (ref "C42") (pin "1") (pinfunction "1_1") (pintype "input"))
      (node (ref "R3") (pin "2") (pinfunction "2_2") (pintype "input"))
      (node (ref "U1") (pin "A12") (pinfunction "VDD_SDRAM_A12") (pintype "input"))
      (node (ref "U1") (pin "C16") (pinfunction "VDD_SDRAM_C16") (pintype "input"))
      (node (ref "U1") (pin "D19") (pinfunction "VDD_SDRAM_D19") (pintype "input"))
      (node (ref "U1") (pin "H14") (pinfunction "VDD_SDRAM_H14") (pintype "input"))
      (node (ref "U1") (pin "N12") (pinfunction "VDD_SDRAM_N12") (pintype "input"))
      (node (ref "U1") (pin "P13") (pinfunction "VDD_SDRAM_P13") (pintype "input"))
      (node (ref "U4") (pin "A1") (pinfunction "VDD_A1") (pintype "input"))
      (node (ref "U4") (pin "A9") (pinfunction "VDDQ_A9") (pintype "input"))
      (node (ref "U4") (pin "C1") (pinfunction "VDDQ_C1") (pintype "input"))
      (node (ref "U4") (pin "C3") (pinfunction "VDDQ_C3") (pintype "input"))
      (node (ref "U4") (pin "C7") (pinfunction "VDDQ_C7") (pintype "input"))
      (node (ref "U4") (pin "C9") (pinfunction "VDDQ_C9") (pintype "input"))
      (node (ref "U4") (pin "E1") (pinfunction "VDD_E1") (pintype "input"))
      (node (ref "U4") (pin "E9") (pinfunction "VDDQ_E9") (pintype "input"))
      (node (ref "U4") (pin "G1") (pinfunction "VDDQ_G1") (pintype "input"))
      (node (ref "U4") (pin "G3") (pinfunction "VDDQ_G3") (pintype "input"))
      (node (ref "U4") (pin "G7") (pinfunction "VDDQ_G7") (pintype "input"))
      (node (ref "U4") (pin "G9") (pinfunction "VDDQ_G9") (pintype "input"))
      (node (ref "U4") (pin "J1") (pinfunction "VDDL_J1") (pintype "input"))
      (node (ref "U4") (pin "J9") (pinfunction "VDD_J9") (pintype "input"))
      (node (ref "U4") (pin "M9") (pinfunction "VDD_M9") (pintype "input"))
      (node (ref "U4") (pin "R1") (pinfunction "VDD_R1") (pintype "input"))
      (node (ref "U8") (pin "2") (pinfunction "VOUT_2") (pintype "input"))
    )
    (net (code "72") (name "3V3") (class "Default")
      (node (ref "C30") (pin "1") (pinfunction "1_1") (pintype "input"))
      (node (ref "C31") (pin "1") (pinfunction "1_1") (pintype "input"))
      (node (ref "C32") (pin "1") (pinfunction "1_1") (pintype "input"))
      (node (ref "C33") (pin "1") (pinfunction "1_1") (pintype "input"))
      (node (ref "C34") (pin "1") (pinfunction "1_1") (pintype "input"))
      (node (ref "C43") (pin "1") (pinfunction "1_1") (pintype "input"))
      (node (ref "C6") (pin "1") (pinfunction "1_1") (pintype "input"))
      (node (ref "CN1") (pin "6") (pinfunction "6_6") (pintype "input"))
      (node (ref "R10") (pin "2") (pinfunction "2_2") (pintype "input"))
      (node (ref "R11") (pin "2") (pinfunction "2_2") (pintype "input"))
      (node (ref "R12") (pin "2") (pinfunction "2_2") (pintype "input"))
      (node (ref "R13") (pin "2") (pinfunction "2_2") (pintype "input"))
      (node (ref "R14") (pin "2") (pinfunction "2_2") (pintype "input"))
      (node (ref "R15") (pin "2") (pinfunction "2_2") (pintype "input"))
      (node (ref "U1") (pin "C5") (pinfunction "VDD_SRAM_C5") (pintype "input"))
      (node (ref "U1") (pin "F3") (pinfunction "VDD_SRAM_F3") (pintype "input"))
      (node (ref "U1") (pin "G18") (pinfunction "VDD33_G18") (pintype "input"))
      (node (ref "U1") (pin "G19") (pinfunction "VDD33_G19") (pintype "input"))
      (node (ref "U1") (pin "H1") (pinfunction "VDD_SRAM_H1") (pintype "input"))
      (node (ref "U1") (pin "L19") (pinfunction "VDD_USBOSC_L19") (pintype "input"))
      (node (ref "U1") (pin "M18") (pinfunction "VDD_OP3_M18") (pintype "input"))
      (node (ref "U1") (pin "N4") (pinfunction "GPC7_N4") (pintype "input"))
      (node (ref "U1") (pin "P18") (pinfunction "nBATT_FLT_P18") (pintype "input"))
      (node (ref "U1") (pin "R13") (pinfunction "AIN9_R13") (pintype "input"))
      (node (ref "U1") (pin "R14") (pinfunction "VDDA_ADC_R14") (pintype "input"))
      (node (ref "U1") (pin "T19") (pinfunction "VDD_OP1_T19") (pintype "input"))
      (node (ref "U1") (pin "U15") (pinfunction "Vref_U15") (pintype "input"))
      (node (ref "U1") (pin "U16") (pinfunction "OM3_U16") (pintype "input"))
      (node (ref "U1") (pin "V14") (pinfunction "AIN7_V14") (pintype "input"))
      (node (ref "U1") (pin "W12") (pinfunction "VDD_SD_W12") (pintype "input"))
      (node (ref "U1") (pin "W19") (pinfunction "VDD_RTC_W19") (pintype "input"))
      (node (ref "U1") (pin "W20") (pinfunction "XTIrtc_W20") (pintype "input"))
      (node (ref "U1") (pin "Y6") (pinfunction "VDD_OP2_Y6") (pintype "input"))
      (node (ref "U3") (pin "12") (pinfunction "VCC_12") (pintype "input"))
      (node (ref "U3") (pin "19") (pinfunction "WP_19") (pintype "input"))
      (node (ref "U3") (pin "37") (pinfunction "VCC_37") (pintype "input"))
      (node (ref "U6") (pin "2") (pinfunction "VOUT_2") (pintype "input"))
    )
    (net (code "73") (name "5V") (class "Default")
      (node (ref "C11") (pin "1") (pinfunction "1_1") (pintype "input"))
      (node (ref "C5") (pin "1") (pinfunction "1_1") (pintype "input"))
      (node (ref "C7") (pin "1") (pinfunction "1_1") (pintype "input"))
      (node (ref "C9") (pin "1") (pinfunction "1_1") (pintype "input"))
      (node (ref "U6") (pin "3") (pinfunction "VIN_3") (pintype "input"))
      (node (ref "U7") (pin "3") (pinfunction "VIN_3") (pintype "input"))
      (node (ref "U8") (pin "3") (pinfunction "VIN_3") (pintype "input"))
      (node (ref "U9") (pin "3") (pinfunction "VIN_3") (pintype "input"))
      (node (ref "USB2") (pin "11") (pinfunction "VBUS_11") (pintype "input"))
      (node (ref "USB2") (pin "2") (pinfunction "VBUS_2") (pintype "input"))
    )
    (net (code "74") (name "GND") (class "Default")
      (node (ref "C1") (pin "1") (pinfunction "1_1") (pintype "input"))
      (node (ref "C10") (pin "2") (pinfunction "2_2") (pintype "input"))
      (node (ref "C11") (pin "2") (pinfunction "2_2") (pintype "input"))
      (node (ref "C12") (pin "2") (pinfunction "2_2") (pintype "input"))
      (node (ref "C13") (pin "2") (pinfunction "2_2") (pintype "input"))
      (node (ref "C14") (pin "2") (pinfunction "2_2") (pintype "input"))
      (node (ref "C15") (pin "2") (pinfunction "2_2") (pintype "input"))
      (node (ref "C17") (pin "2") (pinfunction "2_2") (pintype "input"))
      (node (ref "C18") (pin "2") (pinfunction "2_2") (pintype "input"))
      (node (ref "C19") (pin "2") (pinfunction "2_2") (pintype "input"))
      (node (ref "C2") (pin "1") (pinfunction "1_1") (pintype "input"))
      (node (ref "C20") (pin "2") (pinfunction "2_2") (pintype "input"))
      (node (ref "C22") (pin "2") (pinfunction "2_2") (pintype "input"))
      (node (ref "C23") (pin "2") (pinfunction "2_2") (pintype "input"))
      (node (ref "C24") (pin "2") (pinfunction "2_2") (pintype "input"))
      (node (ref "C25") (pin "2") (pinfunction "2_2") (pintype "input"))
      (node (ref "C26") (pin "2") (pinfunction "2_2") (pintype "input"))
      (node (ref "C27") (pin "2") (pinfunction "2_2") (pintype "input"))
      (node (ref "C28") (pin "2") (pinfunction "2_2") (pintype "input"))
      (node (ref "C3") (pin "1") (pinfunction "1_1") (pintype "input"))
      (node (ref "C30") (pin "2") (pinfunction "2_2") (pintype "input"))
      (node (ref "C31") (pin "2") (pinfunction "2_2") (pintype "input"))
      (node (ref "C32") (pin "2") (pinfunction "2_2") (pintype "input"))
      (node (ref "C33") (pin "2") (pinfunction "2_2") (pintype "input"))
      (node (ref "C34") (pin "2") (pinfunction "2_2") (pintype "input"))
      (node (ref "C35") (pin "2") (pinfunction "2_2") (pintype "input"))
      (node (ref "C36") (pin "2") (pinfunction "2_2") (pintype "input"))
      (node (ref "C37") (pin "2") (pinfunction "2_2") (pintype "input"))
      (node (ref "C38") (pin "2") (pinfunction "2_2") (pintype "input"))
      (node (ref "C39") (pin "2") (pinfunction "2_2") (pintype "input"))
      (node (ref "C40") (pin "2") (pinfunction "2_2") (pintype "input"))
      (node (ref "C41") (pin "2") (pinfunction "2_2") (pintype "input"))
      (node (ref "C42") (pin "2") (pinfunction "2_2") (pintype "input"))
      (node (ref "C43") (pin "2") (pinfunction "2_2") (pintype "input"))
      (node (ref "C44") (pin "2") (pinfunction "2_2") (pintype "input"))
      (node (ref "C45") (pin "2") (pinfunction "2_2") (pintype "input"))
      (node (ref "C5") (pin "2") (pinfunction "2_2") (pintype "input"))
      (node (ref "C6") (pin "2") (pinfunction "2_2") (pintype "input"))
      (node (ref "C7") (pin "2") (pinfunction "2_2") (pintype "input"))
      (node (ref "C8") (pin "2") (pinfunction "2_2") (pintype "input"))
      (node (ref "C9") (pin "2") (pinfunction "2_2") (pintype "input"))
      (node (ref "CN1") (pin "7") (pinfunction "7_7") (pintype "input"))
      (node (ref "H1") (pin "1") (pinfunction "1_1") (pintype "input"))
      (node (ref "LED1") (pin "1") (pinfunction "K_1") (pintype "input"))
      (node (ref "LED2") (pin "1") (pinfunction "K_1") (pintype "input"))
      (node (ref "LED3") (pin "1") (pinfunction "K_1") (pintype "input"))
      (node (ref "R1") (pin "2") (pinfunction "2_2") (pintype "input"))
      (node (ref "R4") (pin "1") (pinfunction "1_1") (pintype "input"))
      (node (ref "R8") (pin "1") (pinfunction "1_1") (pintype "input"))
      (node (ref "R9") (pin "1") (pinfunction "1_1") (pintype "input"))
      (node (ref "U1") (pin "B11") (pinfunction "VSS_SDRAM_B11") (pintype "input"))
      (node (ref "U1") (pin "B5") (pinfunction "VSS_SRAM_B5") (pintype "input"))
      (node (ref "U1") (pin "C15") (pinfunction "VSS_SDRAM_C15") (pintype "input"))
      (node (ref "U1") (pin "D18") (pinfunction "VSS_SDRAM_D18") (pintype "input"))
      (node (ref "U1") (pin "E2") (pinfunction "VSS_SRAM_E2") (pintype "input"))
      (node (ref "U1") (pin "H11") (pinfunction "VSSi_H11") (pintype "input"))
      (node (ref "U1") (pin "H13") (pinfunction "VSSi_H13") (pintype "input"))
      (node (ref "U1") (pin "H18") (pinfunction "VSS33T_H18") (pintype "input"))
      (node (ref "U1") (pin "J17") (pinfunction "VSS33T_J17") (pintype "input"))
      (node (ref "U1") (pin "J3") (pinfunction "VSSi_J3") (pintype "input"))
      (node (ref "U1") (pin "J7") (pinfunction "VSSi_J7") (pintype "input"))
      (node (ref "U1") (pin "K20") (pinfunction "VSSIP_UDEV_K20") (pintype "input"))
      (node (ref "U1") (pin "K3") (pinfunction "VSSiarm_K3") (pintype "input"))
      (node (ref "U1") (pin "L1") (pinfunction "GPC6_L1") (pintype "input"))
      (node (ref "U1") (pin "L20") (pinfunction "VSS33C_L20") (pintype "input"))
      (node (ref "U1") (pin "L3") (pinfunction "VSSiarm_L3") (pintype "input"))
      (node (ref "U1") (pin "L6") (pinfunction "VSSi_L6") (pintype "input"))
      (node (ref "U1") (pin "M19") (pinfunction "VSS_OP3_M19") (pintype "input"))
      (node (ref "U1") (pin "M6") (pinfunction "GPC5_M6") (pintype "input"))
      (node (ref "U1") (pin "M8") (pinfunction "VSSi_M8") (pintype "input"))
      (node (ref "U1") (pin "N10") (pinfunction "VSSi_N10") (pintype "input"))
      (node (ref "U1") (pin "N11") (pinfunction "AIN3_N11") (pintype "input"))
      (node (ref "U1") (pin "N13") (pinfunction "VSSi_N13") (pintype "input"))
      (node (ref "U1") (pin "P11") (pinfunction "VSSA_ADC_P11") (pintype "input"))
      (node (ref "U1") (pin "P12") (pinfunction "AIN5_P12") (pintype "input"))
      (node (ref "U1") (pin "P15") (pinfunction "EXTCLK_P15") (pintype "input"))
      (node (ref "U1") (pin "P3") (pinfunction "VSSiarm_P3") (pintype "input"))
      (node (ref "U1") (pin "P4") (pinfunction "VSSiarm_P4") (pintype "input"))
      (node (ref "U1") (pin "R17") (pinfunction "OM0_R17") (pintype "input"))
      (node (ref "U1") (pin "R20") (pinfunction "VSSalive_R20") (pintype "input"))
      (node (ref "U1") (pin "T20") (pinfunction "VSS_OP1_T20") (pintype "input"))
      (node (ref "U1") (pin "U14") (pinfunction "AIN1_U14") (pintype "input"))
      (node (ref "U1") (pin "U17") (pinfunction "OM1_U17") (pintype "input"))
      (node (ref "U1") (pin "U7") (pinfunction "VSSiarm_U7") (pintype "input"))
      (node (ref "U1") (pin "U8") (pinfunction "VSSiarm_U8") (pintype "input"))
      (node (ref "U1") (pin "U9") (pinfunction "VSSiarm_U9") (pintype "input"))
      (node (ref "U1") (pin "V15") (pinfunction "VSS_MPLL_V15") (pintype "input"))
      (node (ref "U1") (pin "V17") (pinfunction "AIN6_V17") (pintype "input"))
      (node (ref "U1") (pin "V18") (pinfunction "OM4_V18") (pintype "input"))
      (node (ref "U1") (pin "V19") (pinfunction "OM2_V19") (pintype "input"))
      (node (ref "U1") (pin "W16") (pinfunction "VSS_UPLL_W16") (pintype "input"))
      (node (ref "U1") (pin "W17") (pinfunction "AIN8_W17") (pintype "input"))
      (node (ref "U1") (pin "W18") (pinfunction "AIN2_W18") (pintype "input"))
      (node (ref "U1") (pin "W7") (pinfunction "VSS_OP2_W7") (pintype "input"))
      (node (ref "U1") (pin "Y13") (pinfunction "VSS_SD_Y13") (pintype "input"))
      (node (ref "U1") (pin "Y18") (pinfunction "AIN4_Y18") (pintype "input"))
      (node (ref "U1") (pin "Y19") (pinfunction "AIN0_Y19") (pintype "input"))
      (node (ref "U3") (pin "13") (pinfunction "VSS_13") (pintype "input"))
      (node (ref "U3") (pin "36") (pinfunction "VSS_36") (pintype "input"))
      (node (ref "U4") (pin "A3") (pinfunction "VSS_A3") (pintype "input"))
      (node (ref "U4") (pin "A7") (pinfunction "VSSQ_A7") (pintype "input"))
      (node (ref "U4") (pin "B2") (pinfunction "VSSQ_B2") (pintype "input"))
      (node (ref "U4") (pin "B8") (pinfunction "VSSQ_B8") (pintype "input"))
      (node (ref "U4") (pin "D2") (pinfunction "VSSQ_D2") (pintype "input"))
      (node (ref "U4") (pin "D8") (pinfunction "VSSQ_D8") (pintype "input"))
      (node (ref "U4") (pin "E3") (pinfunction "VSS_E3") (pintype "input"))
      (node (ref "U4") (pin "E7") (pinfunction "VSSQ_E7") (pintype "input"))
      (node (ref "U4") (pin "F2") (pinfunction "VSSQ_F2") (pintype "input"))
      (node (ref "U4") (pin "F8") (pinfunction "VSSQ_F8") (pintype "input"))
      (node (ref "U4") (pin "H2") (pinfunction "VSSQ_H2") (pintype "input"))
      (node (ref "U4") (pin "H8") (pinfunction "VSSQ_H8") (pintype "input"))
      (node (ref "U4") (pin "J3") (pinfunction "VSS_J3") (pintype "input"))
      (node (ref "U4") (pin "J7") (pinfunction "VSSDL_J7") (pintype "input"))
      (node (ref "U4") (pin "K9") (pinfunction "ODT_K9") (pintype "input"))
      (node (ref "U4") (pin "N1") (pinfunction "VSS_N1") (pintype "input"))
      (node (ref "U4") (pin "P9") (pinfunction "VSS_P9") (pintype "input"))
      (node (ref "U6") (pin "1") (pinfunction "VSS_1") (pintype "input"))
      (node (ref "U7") (pin "1") (pinfunction "VSS_1") (pintype "input"))
      (node (ref "U8") (pin "1") (pinfunction "VSS_1") (pintype "input"))
      (node (ref "U9") (pin "1") (pinfunction "VSS_1") (pintype "input"))
      (node (ref "USB2") (pin "1") (pinfunction "GND_1") (pintype "input"))
      (node (ref "USB2") (pin "12") (pinfunction "GND_12") (pintype "input"))
      (node (ref "USB2") (pin "13") (pinfunction "SHELL_13") (pintype "input"))
      (node (ref "USB2") (pin "14") (pinfunction "SHELL_14") (pintype "input"))
    )
    (net (code "75") (name "Net-(LED1-A)") (class "Default")
      (node (ref "LED1") (pin "2") (pinfunction "A_2") (pintype "input"))
      (node (ref "R5") (pin "2") (pinfunction "2_2") (pintype "input"))
    )
    (net (code "76") (name "Net-(LED2-A)") (class "Default")
      (node (ref "LED2") (pin "2") (pinfunction "A_2") (pintype "input"))
      (node (ref "R6") (pin "2") (pinfunction "2_2") (pintype "input"))
    )
    (net (code "77") (name "Net-(LED3-A)") (class "Default")
      (node (ref "LED3") (pin "2") (pinfunction "A_2") (pintype "input"))
      (node (ref "R7") (pin "2") (pinfunction "2_2") (pintype "input"))
    )
    (net (code "78") (name "Net-(U1-REXT)") (class "Default")
      (node (ref "R1") (pin "1") (pinfunction "1_1") (pintype "input"))
      (node (ref "U1") (pin "H20") (pinfunction "REXT_H20") (pintype "output"))
    )
    (net (code "79") (name "Net-(U1-UPLLCAP)") (class "Default")
      (node (ref "C45") (pin "1") (pinfunction "1_1") (pintype "input"))
      (node (ref "U1") (pin "V16") (pinfunction "UPLLCAP_V16") (pintype "input"))
    )
    (net (code "80") (name "Net-(U1-XI_UDEV)") (class "Default")
      (node (ref "C1") (pin "2") (pinfunction "2_2") (pintype "input"))
      (node (ref "U1") (pin "K19") (pinfunction "XI_UDEV_K19") (pintype "output"))
      (node (ref "U1") (pin "V20") (pinfunction "XTIpll_V20") (pintype "input"))
      (node (ref "X2") (pin "2") (pinfunction "OSC2_2") (pintype "input"))
    )
    (net (code "81") (name "Net-(U1-XTOpll)") (class "Default")
      (node (ref "C2") (pin "2") (pinfunction "2_2") (pintype "input"))
      (node (ref "U1") (pin "U18") (pinfunction "XTOpll_U18") (pintype "output"))
      (node (ref "X2") (pin "1") (pinfunction "OSC1_1") (pintype "input"))
    )
    (net (code "82") (name "Net-(U1-nRESET)") (class "Default")
      (node (ref "C44") (pin "1") (pinfunction "1_1") (pintype "input"))
      (node (ref "R14") (pin "1") (pinfunction "1_1") (pintype "input"))
      (node (ref "U1") (pin "M14") (pinfunction "nRESET_M14") (pintype "input"))
    )
    (net (code "83") (name "Net-(U1-nWAIT)") (class "Default")
      (node (ref "R15") (pin "1") (pinfunction "1_1") (pintype "input"))
      (node (ref "U1") (pin "D3") (pinfunction "nWAIT_D3") (pintype "input"))
    )
    (net (code "84") (name "Net-(U4-VREF)") (class "Default")
      (node (ref "C3") (pin "2") (pinfunction "2_2") (pintype "input"))
      (node (ref "C4") (pin "2") (pinfunction "2_2") (pintype "input"))
      (node (ref "R3") (pin "1") (pinfunction "1_1") (pintype "input"))
      (node (ref "R4") (pin "2") (pinfunction "2_2") (pintype "input"))
      (node (ref "U4") (pin "J2") (pinfunction "VREF_J2") (pintype "input"))
    )
    (net (code "85") (name "Net-(USB2-CC1)") (class "Default")
      (node (ref "R8") (pin "2") (pinfunction "2_2") (pintype "input"))
      (node (ref "USB2") (pin "4") (pinfunction "CC1_4") (pintype "input"))
    )
    (net (code "86") (name "Net-(USB2-CC2)") (class "Default")
      (node (ref "R9") (pin "2") (pinfunction "2_2") (pintype "input"))
      (node (ref "USB2") (pin "10") (pinfunction "CC2_10") (pintype "input"))
    )
    (net (code "87") (name "unconnected-(CN1-Pad8)") (class "Default")
      (node (ref "CN1") (pin "8") (pinfunction "8_8") (pintype "input"))
    )
    (net (code "88") (name "unconnected-(CN1-Pad9)") (class "Default")
      (node (ref "CN1") (pin "9") (pinfunction "9_9") (pintype "input"))
    )
    (net (code "89") (name "unconnected-(U1-CLKOUT0{slash}GPH13-PadV8)") (class "Default")
      (node (ref "U1") (pin "V8") (pinfunction "CLKOUT0/GPH13_V8") (pintype "input+no_connect"))
    )
    (net (code "90") (name "unconnected-(U1-CLKOUT1{slash}GPH14-PadY7)") (class "Default")
      (node (ref "U1") (pin "Y7") (pinfunction "CLKOUT1/GPH14_Y7") (pintype "input+no_connect"))
    )
    (net (code "91") (name "unconnected-(U1-DQM2{slash}GPA25-PadB16)") (class "Default")
      (node (ref "U1") (pin "B16") (pinfunction "DQM2/GPA25_B16") (pintype "input+no_connect"))
    )
    (net (code "92") (name "unconnected-(U1-DQM3{slash}GPA26-PadD14)") (class "Default")
      (node (ref "U1") (pin "D14") (pinfunction "DQM3/GPA26_D14") (pintype "input+no_connect"))
    )
    (net (code "93") (name "unconnected-(U1-PWR_EN-PadM15)") (class "Default")
      (node (ref "U1") (pin "M15") (pinfunction "PWR_EN_M15") (pintype "input+no_connect"))
    )
    (net (code "94") (name "unconnected-(U1-RADDR0{slash}GPA0-PadB3)") (class "Default")
      (node (ref "U1") (pin "B3") (pinfunction "RADDR0/GPA0_B3") (pintype "input+no_connect"))
    )
    (net (code "95") (name "unconnected-(U1-RADDR1-PadD7)") (class "Default")
      (node (ref "U1") (pin "D7") (pinfunction "RADDR1_D7") (pintype "input+no_connect"))
    )
    (net (code "96") (name "unconnected-(U1-RADDR2-PadA3)") (class "Default")
      (node (ref "U1") (pin "A3") (pinfunction "RADDR2_A3") (pintype "input+no_connect"))
    )
    (net (code "97") (name "unconnected-(U1-RADDR3-PadH8)") (class "Default")
      (node (ref "U1") (pin "H8") (pinfunction "RADDR3_H8") (pintype "input+no_connect"))
    )
    (net (code "98") (name "unconnected-(U1-RADDR4-PadC4)") (class "Default")
      (node (ref "U1") (pin "C4") (pinfunction "RADDR4_C4") (pintype "input+no_connect"))
    )
    (net (code "99") (name "unconnected-(U1-RADDR5-PadG8)") (class "Default")
      (node (ref "U1") (pin "G8") (pinfunction "RADDR5_G8") (pintype "input+no_connect"))
    )
    (net (code "100") (name "unconnected-(U1-RADDR6-PadB4)") (class "Default")
      (node (ref "U1") (pin "B4") (pinfunction "RADDR6_B4") (pintype "input+no_connect"))
    )
    (net (code "101") (name "unconnected-(U1-RADDR7-PadF8)") (class "Default")
      (node (ref "U1") (pin "F8") (pinfunction "RADDR7_F8") (pintype "input+no_connect"))
    )
    (net (code "102") (name "unconnected-(U1-RADDR8-PadA4)") (class "Default")
      (node (ref "U1") (pin "A4") (pinfunction "RADDR8_A4") (pintype "input+no_connect"))
    )
    (net (code "103") (name "unconnected-(U1-RADDR9-PadD8)") (class "Default")
      (node (ref "U1") (pin "D8") (pinfunction "RADDR9_D8") (pintype "input+no_connect"))
    )
    (net (code "104") (name "unconnected-(U1-RADDR10-PadA5)") (class "Default")
      (node (ref "U1") (pin "A5") (pinfunction "RADDR10_A5") (pintype "input+no_connect"))
    )
    (net (code "105") (name "unconnected-(U1-RADDR11-PadH9)") (class "Default")
      (node (ref "U1") (pin "H9") (pinfunction "RADDR11_H9") (pintype "input+no_connect"))
    )
    (net (code "106") (name "unconnected-(U1-RADDR12-PadC6)") (class "Default")
      (node (ref "U1") (pin "C6") (pinfunction "RADDR12_C6") (pintype "input+no_connect"))
    )
    (net (code "107") (name "unconnected-(U1-RADDR13-PadG9)") (class "Default")
      (node (ref "U1") (pin "G9") (pinfunction "RADDR13_G9") (pintype "input+no_connect"))
    )
    (net (code "108") (name "unconnected-(U1-RADDR14-PadB6)") (class "Default")
      (node (ref "U1") (pin "B6") (pinfunction "RADDR14_B6") (pintype "input+no_connect"))
    )
    (net (code "109") (name "unconnected-(U1-RADDR15-PadF9)") (class "Default")
      (node (ref "U1") (pin "F9") (pinfunction "RADDR15_F9") (pintype "input+no_connect"))
    )
    (net (code "110") (name "unconnected-(U1-RADDR16{slash}GPA1-PadA6)") (class "Default")
      (node (ref "U1") (pin "A6") (pinfunction "RADDR16/GPA1_A6") (pintype "input+no_connect"))
    )
    (net (code "111") (name "unconnected-(U1-RADDR17{slash}GPA2-PadD9)") (class "Default")
      (node (ref "U1") (pin "D9") (pinfunction "RADDR17/GPA2_D9") (pintype "input+no_connect"))
    )
    (net (code "112") (name "unconnected-(U1-RADDR18{slash}GPA3-PadC7)") (class "Default")
      (node (ref "U1") (pin "C7") (pinfunction "RADDR18/GPA3_C7") (pintype "input+no_connect"))
    )
    (net (code "113") (name "unconnected-(U1-RADDR19{slash}GPA4-PadC9)") (class "Default")
      (node (ref "U1") (pin "C9") (pinfunction "RADDR19/GPA4_C9") (pintype "input+no_connect"))
    )
    (net (code "114") (name "unconnected-(U1-RADDR20{slash}GPA5-PadB7)") (class "Default")
      (node (ref "U1") (pin "B7") (pinfunction "RADDR20/GPA5_B7") (pintype "input+no_connect"))
    )
    (net (code "115") (name "unconnected-(U1-RADDR21{slash}GPA6-PadH10)") (class "Default")
      (node (ref "U1") (pin "H10") (pinfunction "RADDR21/GPA6_H10") (pintype "input+no_connect"))
    )
    (net (code "116") (name "unconnected-(U1-RADDR22{slash}GPA7-PadA7)") (class "Default")
      (node (ref "U1") (pin "A7") (pinfunction "RADDR22/GPA7_A7") (pintype "input+no_connect"))
    )
    (net (code "117") (name "unconnected-(U1-RADDR23{slash}GPA8-PadG10)") (class "Default")
      (node (ref "U1") (pin "G10") (pinfunction "RADDR23/GPA8_G10") (pintype "input+no_connect"))
    )
    (net (code "118") (name "unconnected-(U1-RADDR24{slash}GPA9-PadC8)") (class "Default")
      (node (ref "U1") (pin "C8") (pinfunction "RADDR24/GPA9_C8") (pintype "input+no_connect"))
    )
    (net (code "119") (name "unconnected-(U1-RADDR25{slash}RDATA_OEN-PadF10)") (class "Default")
      (node (ref "U1") (pin "F10") (pinfunction "RADDR25/RDATA_OEN_F10") (pintype "input+no_connect"))
    )
    (net (code "120") (name "unconnected-(U1-RDATA8-PadG3)") (class "Default")
      (node (ref "U1") (pin "G3") (pinfunction "RDATA8_G3") (pintype "input+no_connect"))
    )
    (net (code "121") (name "unconnected-(U1-RDATA9-PadK4)") (class "Default")
      (node (ref "U1") (pin "K4") (pinfunction "RDATA9_K4") (pintype "input+no_connect"))
    )
    (net (code "122") (name "unconnected-(U1-RDATA10-PadF1)") (class "Default")
      (node (ref "U1") (pin "F1") (pinfunction "RDATA10_F1") (pintype "input+no_connect"))
    )
    (net (code "123") (name "unconnected-(U1-RDATA11-PadJ6)") (class "Default")
      (node (ref "U1") (pin "J6") (pinfunction "RDATA11_J6") (pintype "input+no_connect"))
    )
    (net (code "124") (name "unconnected-(U1-RDATA12-PadF2)") (class "Default")
      (node (ref "U1") (pin "F2") (pinfunction "RDATA12_F2") (pintype "input+no_connect"))
    )
    (net (code "125") (name "unconnected-(U1-RDATA13-PadJ4)") (class "Default")
      (node (ref "U1") (pin "J4") (pinfunction "RDATA13_J4") (pintype "input+no_connect"))
    )
    (net (code "126") (name "unconnected-(U1-RDATA14-PadE1)") (class "Default")
      (node (ref "U1") (pin "E1") (pinfunction "RDATA14_E1") (pintype "input+no_connect"))
    )
    (net (code "127") (name "unconnected-(U1-RDATA15-PadH7)") (class "Default")
      (node (ref "U1") (pin "H7") (pinfunction "RDATA15_H7") (pintype "input+no_connect"))
    )
    (net (code "128") (name "unconnected-(U1-RSMBWAIT{slash}GPM0-PadC2)") (class "Default")
      (node (ref "U1") (pin "C2") (pinfunction "RSMBWAIT/GPM0_C2") (pintype "input+no_connect"))
    )
    (net (code "129") (name "unconnected-(U1-RSMCLK{slash}GPA23-PadB1)") (class "Default")
      (node (ref "U1") (pin "B1") (pinfunction "RSMCLK/GPA23_B1") (pintype "input+no_connect"))
    )
    (net (code "130") (name "unconnected-(U1-RSMVAD{slash}GPA24-PadE4)") (class "Default")
      (node (ref "U1") (pin "E4") (pinfunction "RSMVAD/GPA24_E4") (pintype "input+no_connect"))
    )
    (net (code "131") (name "unconnected-(U1-SADDR13-PadA9)") (class "Default")
      (node (ref "U1") (pin "A9") (pinfunction "SADDR13_A9") (pintype "input+no_connect"))
    )
    (net (code "132") (name "unconnected-(U1-SDATA16{slash}GPK0-PadD20)") (class "Default")
      (node (ref "U1") (pin "D20") (pinfunction "SDATA16/GPK0_D20") (pintype "input+no_connect"))
    )
    (net (code "133") (name "unconnected-(U1-SDATA17{slash}GPK1-PadF17)") (class "Default")
      (node (ref "U1") (pin "F17") (pinfunction "SDATA17/GPK1_F17") (pintype "input+no_connect"))
    )
    (net (code "134") (name "unconnected-(U1-SDATA18{slash}GPK2-PadE18)") (class "Default")
      (node (ref "U1") (pin "E18") (pinfunction "SDATA18/GPK2_E18") (pintype "input+no_connect"))
    )
    (net (code "135") (name "unconnected-(U1-SDATA19{slash}GPK3-PadG15)") (class "Default")
      (node (ref "U1") (pin "G15") (pinfunction "SDATA19/GPK3_G15") (pintype "input+no_connect"))
    )
    (net (code "136") (name "unconnected-(U1-SDATA20{slash}GPK4-PadE19)") (class "Default")
      (node (ref "U1") (pin "E19") (pinfunction "SDATA20/GPK4_E19") (pintype "input+no_connect"))
    )
    (net (code "137") (name "unconnected-(U1-SDATA21{slash}GPK5-PadG17)") (class "Default")
      (node (ref "U1") (pin "G17") (pinfunction "SDATA21/GPK5_G17") (pintype "input+no_connect"))
    )
    (net (code "138") (name "unconnected-(U1-SDATA22{slash}GPK6-PadE20)") (class "Default")
      (node (ref "U1") (pin "E20") (pinfunction "SDATA22/GPK6_E20") (pintype "input+no_connect"))
    )
    (net (code "139") (name "unconnected-(U1-SDATA23{slash}GPK7-PadH15)") (class "Default")
      (node (ref "U1") (pin "H15") (pinfunction "SDATA23/GPK7_H15") (pintype "input+no_connect"))
    )
    (net (code "140") (name "unconnected-(U1-SDATA24{slash}GPK8-PadF18)") (class "Default")
      (node (ref "U1") (pin "F18") (pinfunction "SDATA24/GPK8_F18") (pintype "input+no_connect"))
    )
    (net (code "141") (name "unconnected-(U1-SDATA25{slash}GPK9-PadH17)") (class "Default")
      (node (ref "U1") (pin "H17") (pinfunction "SDATA25/GPK9_H17") (pintype "input+no_connect"))
    )
    (net (code "142") (name "unconnected-(U1-SDATA26{slash}GPK10-PadF19)") (class "Default")
      (node (ref "U1") (pin "F19") (pinfunction "SDATA26/GPK10_F19") (pintype "input+no_connect"))
    )
    (net (code "143") (name "unconnected-(U1-SDATA27{slash}GPK11-PadJ14)") (class "Default")
      (node (ref "U1") (pin "J14") (pinfunction "SDATA27/GPK11_J14") (pintype "input+no_connect"))
    )
    (net (code "144") (name "unconnected-(U1-SDATA28{slash}GPK12-PadF20)") (class "Default")
      (node (ref "U1") (pin "F20") (pinfunction "SDATA28/GPK12_F20") (pintype "input+no_connect"))
    )
    (net (code "145") (name "unconnected-(U1-SDATA29{slash}GPK13-PadJ15)") (class "Default")
      (node (ref "U1") (pin "J15") (pinfunction "SDATA29/GPK13_J15") (pintype "input+no_connect"))
    )
    (net (code "146") (name "unconnected-(U1-SDATA30{slash}GPK14-PadG20)") (class "Default")
      (node (ref "U1") (pin "G20") (pinfunction "SDATA30/GPK14_G20") (pintype "input+no_connect"))
    )
    (net (code "147") (name "unconnected-(U1-SDATA31{slash}GPK15-PadJ18)") (class "Default")
      (node (ref "U1") (pin "J18") (pinfunction "SDATA31/GPK15_J18") (pintype "input+no_connect"))
    )
    (net (code "148") (name "unconnected-(U1-TOUT3{slash}GPB3-PadW1)") (class "Default")
      (node (ref "U1") (pin "W1") (pinfunction "TOUT3/GPB3_W1") (pintype "input+no_connect"))
    )
    (net (code "149") (name "unconnected-(U1-XO_UDEV-PadK18)") (class "Default")
      (node (ref "U1") (pin "K18") (pinfunction "XO_UDEV_K18") (pintype "output+no_connect"))
    )
    (net (code "150") (name "unconnected-(U1-XTOrtc-PadT17)") (class "Default")
      (node (ref "U1") (pin "T17") (pinfunction "XTOrtc_T17") (pintype "output+no_connect"))
    )
    (net (code "151") (name "unconnected-(U1-nRBE0-PadC3)") (class "Default")
      (node (ref "U1") (pin "C3") (pinfunction "nRBE0_C3") (pintype "input+no_connect"))
    )
    (net (code "152") (name "unconnected-(U1-nRBE1-PadF7)") (class "Default")
      (node (ref "U1") (pin "F7") (pinfunction "nRBE1_F7") (pintype "input+no_connect"))
    )
    (net (code "153") (name "unconnected-(U1-nRCS0-PadD5)") (class "Default")
      (node (ref "U1") (pin "D5") (pinfunction "nRCS0_D5") (pintype "input+no_connect"))
    )
    (net (code "154") (name "unconnected-(U1-nRCS1{slash}GPA12-PadB2)") (class "Default")
      (node (ref "U1") (pin "B2") (pinfunction "nRCS1/GPA12_B2") (pintype "input+no_connect"))
    )
    (net (code "155") (name "unconnected-(U1-nRCS2{slash}GPA13-PadD4)") (class "Default")
      (node (ref "U1") (pin "D4") (pinfunction "nRCS2/GPA13_D4") (pintype "input+no_connect"))
    )
    (net (code "156") (name "unconnected-(U1-nRCS3{slash}GPA14-PadF4)") (class "Default")
      (node (ref "U1") (pin "F4") (pinfunction "nRCS3/GPA14_F4") (pintype "input+no_connect"))
    )
    (net (code "157") (name "unconnected-(U1-nRCS4{slash}GPA15-PadC1)") (class "Default")
      (node (ref "U1") (pin "C1") (pinfunction "nRCS4/GPA15_C1") (pintype "input+no_connect"))
    )
    (net (code "158") (name "unconnected-(U1-nRCS5{slash}GPA16-PadG6)") (class "Default")
      (node (ref "U1") (pin "G6") (pinfunction "nRCS5/GPA16_G6") (pintype "input+no_connect"))
    )
    (net (code "159") (name "unconnected-(U1-nROE-PadD6)") (class "Default")
      (node (ref "U1") (pin "D6") (pinfunction "nROE_D6") (pintype "input+no_connect"))
    )
    (net (code "160") (name "unconnected-(U1-nRSTOUT{slash}GPA21-PadN18)") (class "Default")
      (node (ref "U1") (pin "N18") (pinfunction "nRSTOUT/GPA21_N18") (pintype "input+no_connect"))
    )
    (net (code "161") (name "unconnected-(U1-nRWE-PadA2)") (class "Default")
      (node (ref "U1") (pin "A2") (pinfunction "nRWE_A2") (pintype "input+no_connect"))
    )
    (net (code "162") (name "unconnected-(U1-nSCS1-PadB15)") (class "Default")
      (node (ref "U1") (pin "B15") (pinfunction "nSCS1_B15") (pintype "input+no_connect"))
    )
    (net (code "163") (name "unconnected-(U1-nXBACK{slash}GPB5-PadU6)") (class "Default")
      (node (ref "U1") (pin "U6") (pinfunction "nXBACK/GPB5_U6") (pintype "input+no_connect"))
    )
    (net (code "164") (name "unconnected-(U1-nXBREQ{slash}RTCK{slash}GPB6-PadV4)") (class "Default")
      (node (ref "U1") (pin "V4") (pinfunction "nXBREQ/RTCK/GPB6_V4") (pintype "input+no_connect"))
    )
    (net (code "165") (name "unconnected-(U1-nXDACK0{slash}I2S0_SDO1{slash}GPB9-PadW4)") (class "Default")
      (node (ref "U1") (pin "W4") (pinfunction "nXDACK0/I2S0_SDO1/GPB9_W4") (pintype "input+no_connect"))
    )
    (net (code "166") (name "unconnected-(U1-nXDREQ0{slash}I2S0_SDO2{slash}GPB10-PadU5)") (class "Default")
      (node (ref "U1") (pin "U5") (pinfunction "nXDREQ0/I2S0_SDO2/GPB10_U5") (pintype "input+no_connect"))
    )
    (net (code "167") (name "unconnected-(U3-NC-Pad1)") (class "Default")
      (node (ref "U3") (pin "1") (pinfunction "NC_1") (pintype "input+no_connect"))
    )
    (net (code "168") (name "unconnected-(U3-NC-Pad2)") (class "Default")
      (node (ref "U3") (pin "2") (pinfunction "NC_2") (pintype "input+no_connect"))
    )
    (net (code "169") (name "unconnected-(U3-NC-Pad3)") (class "Default")
      (node (ref "U3") (pin "3") (pinfunction "NC_3") (pintype "input+no_connect"))
    )
    (net (code "170") (name "unconnected-(U3-NC-Pad4)") (class "Default")
      (node (ref "U3") (pin "4") (pinfunction "NC_4") (pintype "input+no_connect"))
    )
    (net (code "171") (name "unconnected-(U3-NC-Pad5)") (class "Default")
      (node (ref "U3") (pin "5") (pinfunction "NC_5") (pintype "input+no_connect"))
    )
    (net (code "172") (name "unconnected-(U3-NC-Pad6)") (class "Default")
      (node (ref "U3") (pin "6") (pinfunction "NC_6") (pintype "input+no_connect"))
    )
    (net (code "173") (name "unconnected-(U3-NC-Pad10)") (class "Default")
      (node (ref "U3") (pin "10") (pinfunction "NC_10") (pintype "input+no_connect"))
    )
    (net (code "174") (name "unconnected-(U3-NC-Pad11)") (class "Default")
      (node (ref "U3") (pin "11") (pinfunction "NC_11") (pintype "input+no_connect"))
    )
    (net (code "175") (name "unconnected-(U3-NC-Pad14)") (class "Default")
      (node (ref "U3") (pin "14") (pinfunction "NC_14") (pintype "input+no_connect"))
    )
    (net (code "176") (name "unconnected-(U3-NC-Pad15)") (class "Default")
      (node (ref "U3") (pin "15") (pinfunction "NC_15") (pintype "input+no_connect"))
    )
    (net (code "177") (name "unconnected-(U3-NC-Pad20)") (class "Default")
      (node (ref "U3") (pin "20") (pinfunction "NC_20") (pintype "input+no_connect"))
    )
    (net (code "178") (name "unconnected-(U3-NC-Pad21)") (class "Default")
      (node (ref "U3") (pin "21") (pinfunction "NC_21") (pintype "input+no_connect"))
    )
    (net (code "179") (name "unconnected-(U3-NC-Pad22)") (class "Default")
      (node (ref "U3") (pin "22") (pinfunction "NC_22") (pintype "input+no_connect"))
    )
    (net (code "180") (name "unconnected-(U3-NC-Pad23)") (class "Default")
      (node (ref "U3") (pin "23") (pinfunction "NC_23") (pintype "input+no_connect"))
    )
    (net (code "181") (name "unconnected-(U3-NC-Pad24)") (class "Default")
      (node (ref "U3") (pin "24") (pinfunction "NC_24") (pintype "input+no_connect"))
    )
    (net (code "182") (name "unconnected-(U3-NC-Pad25)") (class "Default")
      (node (ref "U3") (pin "25") (pinfunction "NC_25") (pintype "input+no_connect"))
    )
    (net (code "183") (name "unconnected-(U3-NC-Pad26)") (class "Default")
      (node (ref "U3") (pin "26") (pinfunction "NC_26") (pintype "input+no_connect"))
    )
    (net (code "184") (name "unconnected-(U3-NC-Pad27)") (class "Default")
      (node (ref "U3") (pin "27") (pinfunction "NC_27") (pintype "input+no_connect"))
    )
    (net (code "185") (name "unconnected-(U3-NC-Pad28)") (class "Default")
      (node (ref "U3") (pin "28") (pinfunction "NC_28") (pintype "input+no_connect"))
    )
    (net (code "186") (name "unconnected-(U3-NC-Pad33)") (class "Default")
      (node (ref "U3") (pin "33") (pinfunction "NC_33") (pintype "input+no_connect"))
    )
    (net (code "187") (name "unconnected-(U3-NC-Pad34)") (class "Default")
      (node (ref "U3") (pin "34") (pinfunction "NC_34") (pintype "input+no_connect"))
    )
    (net (code "188") (name "unconnected-(U3-NC-Pad35)") (class "Default")
      (node (ref "U3") (pin "35") (pinfunction "NC_35") (pintype "input+no_connect"))
    )
    (net (code "189") (name "unconnected-(U3-NC-Pad38)") (class "Default")
      (node (ref "U3") (pin "38") (pinfunction "NC_38") (pintype "input+no_connect"))
    )
    (net (code "190") (name "unconnected-(U3-NC-Pad39)") (class "Default")
      (node (ref "U3") (pin "39") (pinfunction "NC_39") (pintype "input+no_connect"))
    )
    (net (code "191") (name "unconnected-(U3-NC-Pad40)") (class "Default")
      (node (ref "U3") (pin "40") (pinfunction "NC_40") (pintype "input+no_connect"))
    )
    (net (code "192") (name "unconnected-(U3-NC-Pad45)") (class "Default")
      (node (ref "U3") (pin "45") (pinfunction "NC_45") (pintype "input+no_connect"))
    )
    (net (code "193") (name "unconnected-(U3-NC-Pad46)") (class "Default")
      (node (ref "U3") (pin "46") (pinfunction "NC_46") (pintype "input+no_connect"))
    )
    (net (code "194") (name "unconnected-(U3-NC-Pad47)") (class "Default")
      (node (ref "U3") (pin "47") (pinfunction "NC_47") (pintype "input+no_connect"))
    )
    (net (code "195") (name "unconnected-(U3-NC-Pad48)") (class "Default")
      (node (ref "U3") (pin "48") (pinfunction "NC_48") (pintype "input+no_connect"))
    )
    (net (code "196") (name "unconnected-(U4-LDQS#-PadE8)") (class "Default")
      (node (ref "U4") (pin "E8") (pinfunction "LDQS#_E8") (pintype "input+no_connect"))
    )
    (net (code "197") (name "unconnected-(U4-NC-PadA2)") (class "Default")
      (node (ref "U4") (pin "A2") (pinfunction "NC_A2") (pintype "input+no_connect"))
    )
    (net (code "198") (name "unconnected-(U4-NC-PadE2)") (class "Default")
      (node (ref "U4") (pin "E2") (pinfunction "NC_E2") (pintype "input+no_connect"))
    )
    (net (code "199") (name "unconnected-(U4-NC-PadL1)") (class "Default")
      (node (ref "U4") (pin "L1") (pinfunction "NC_L1") (pintype "input+no_connect"))
    )
    (net (code "200") (name "unconnected-(U4-NC-PadR3)") (class "Default")
      (node (ref "U4") (pin "R3") (pinfunction "NC_R3") (pintype "input+no_connect"))
    )
    (net (code "201") (name "unconnected-(U4-NC-PadR7)") (class "Default")
      (node (ref "U4") (pin "R7") (pinfunction "NC_R7") (pintype "input+no_connect"))
    )
    (net (code "202") (name "unconnected-(U4-NC-PadR8)") (class "Default")
      (node (ref "U4") (pin "R8") (pinfunction "NC_R8") (pintype "input+no_connect"))
    )
    (net (code "203") (name "unconnected-(U4-UDQS#-PadA8)") (class "Default")
      (node (ref "U4") (pin "A8") (pinfunction "UDQS#_A8") (pintype "input+no_connect"))
    )
    (net (code "204") (name "unconnected-(USB2-SBU1-Pad9)") (class "Default")
      (node (ref "USB2") (pin "9") (pinfunction "SBU1_9") (pintype "input"))
    )
    (net (code "205") (name "unconnected-(USB2-SBU2-Pad3)") (class "Default")
      (node (ref "USB2") (pin "3") (pinfunction "SBU2_3") (pintype "input"))
    )
  )
)
